# MSSRP-Temperature_System_beta_2layer.net
KiCad netlist of a schematic drawn in EAGLE
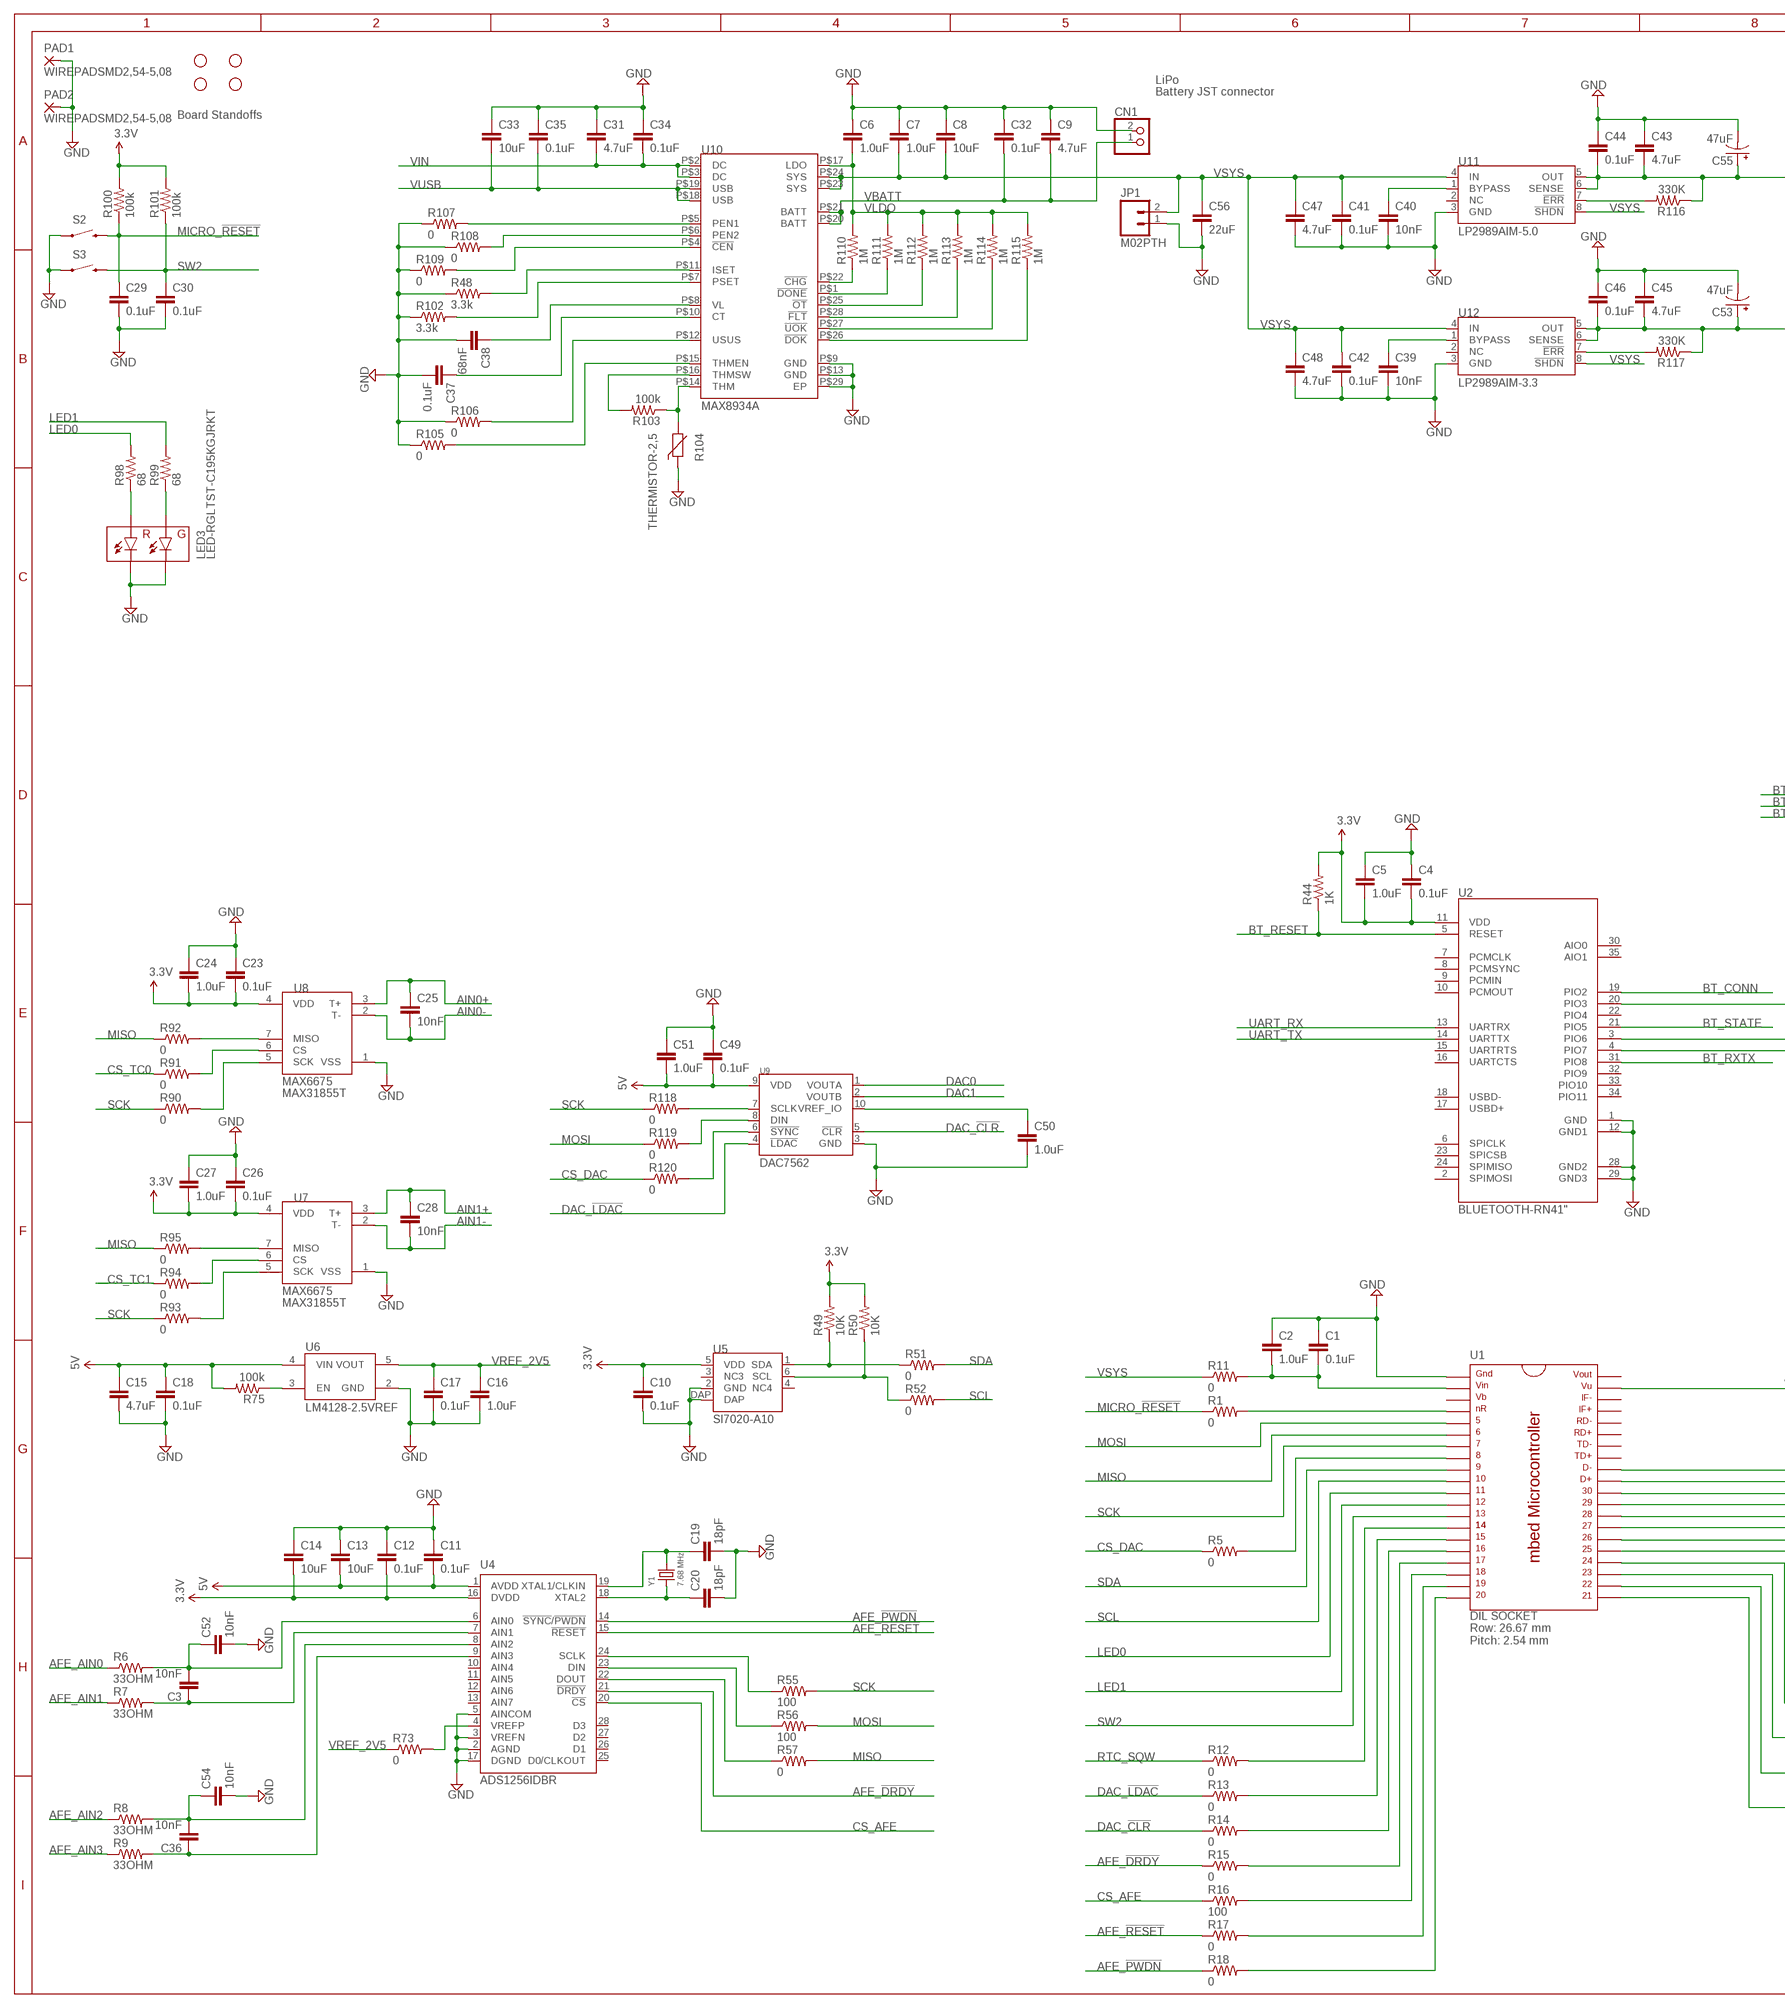
[diagram p0: schematic, sheet 1, part 1 of 2]
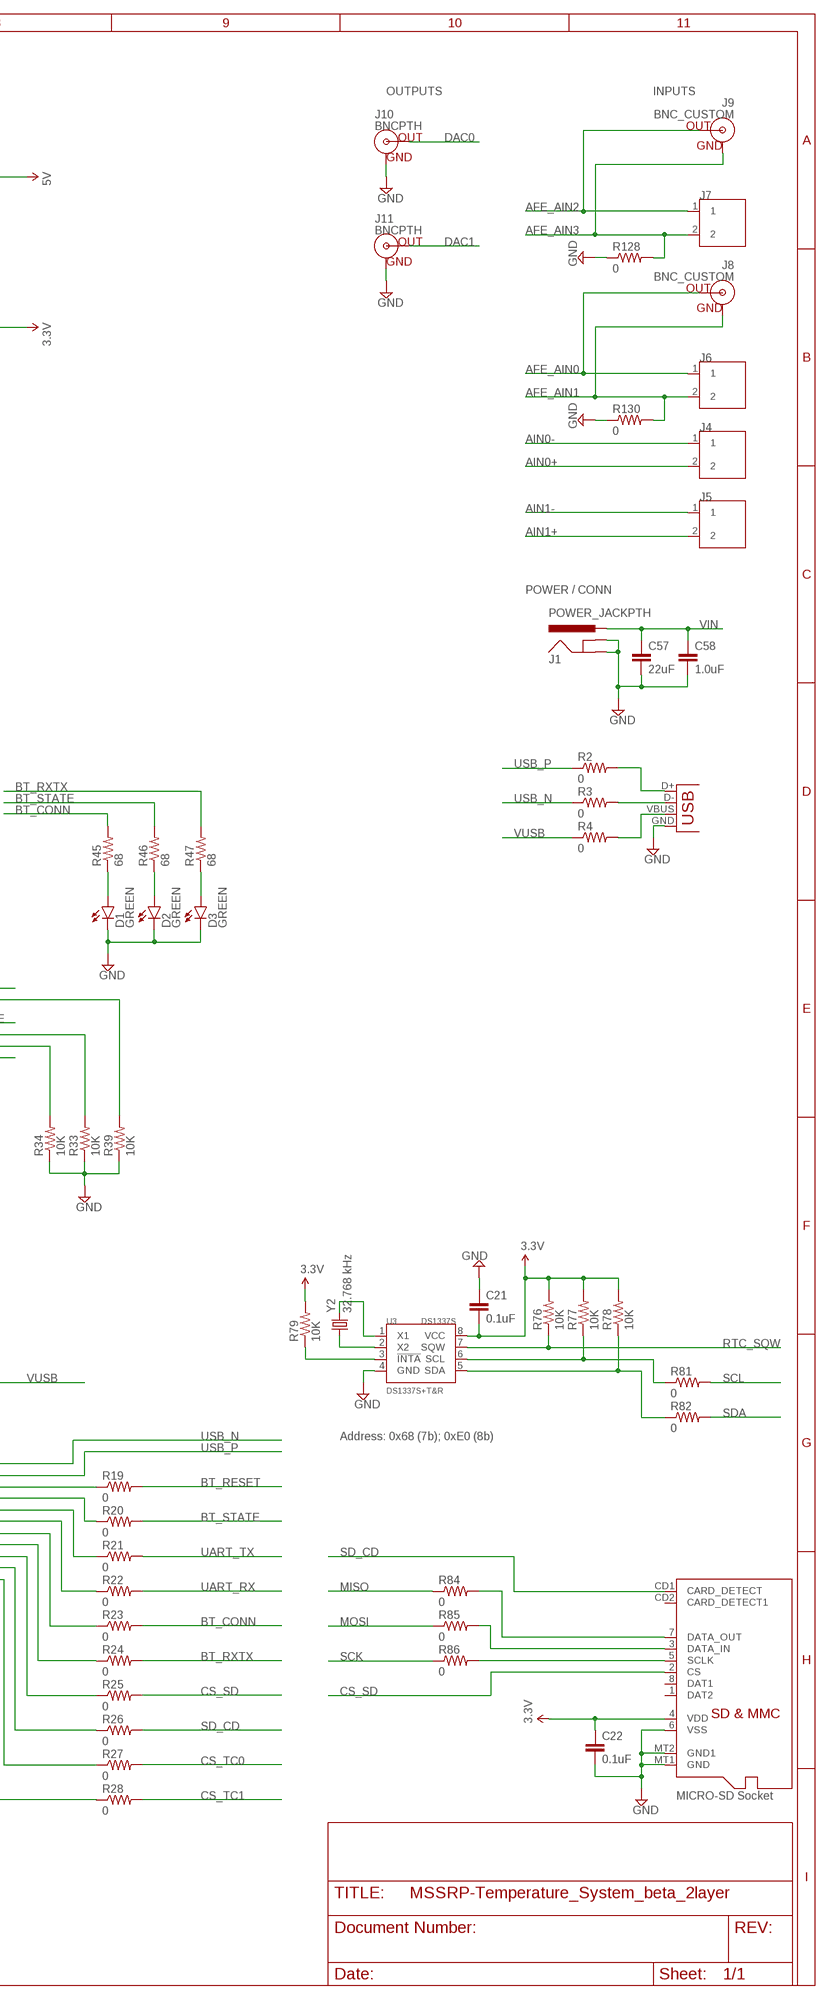
[diagram p1: schematic, sheet 1, part 2 of 2]

(export (version "E")
  (design (tool "Eeschema 10.0.6"))
  (components
    (comp (ref "C1")
      (value "0.1uF")
      (footprint "eagle-import:0603-CAP")
      (libsource (lib "eagle-import") (part "0.1UF-25V-5%(0603)"))
    )
    (comp (ref "C2")
      (value "1.0uF")
      (footprint "eagle-import:0603-CAP")
      (libsource (lib "eagle-import") (part "1.0UF-16V-10%(0603)"))
    )
    (comp (ref "C3")
      (value "10nF")
      (footprint "eagle-import:0603-CAP")
      (libsource (lib "eagle-import") (part "10NF/10000PF-50V-10%(0603)"))
    )
    (comp (ref "C4")
      (value "0.1uF")
      (footprint "eagle-import:0603-CAP")
      (libsource (lib "eagle-import") (part "0.1UF-25V-5%(0603)"))
    )
    (comp (ref "C5")
      (value "1.0uF")
      (footprint "eagle-import:0603-CAP")
      (libsource (lib "eagle-import") (part "1.0UF-16V-10%(0603)"))
    )
    (comp (ref "C6")
      (value "1.0uF")
      (footprint "eagle-import:0603-CAP")
      (libsource (lib "eagle-import") (part "1.0UF-16V-10%(0603)"))
    )
    (comp (ref "C7")
      (value "1.0uF")
      (footprint "eagle-import:0603-CAP")
      (libsource (lib "eagle-import") (part "1.0UF-16V-10%(0603)"))
    )
    (comp (ref "C8")
      (value "10uF")
      (footprint "eagle-import:0603-CAP")
      (libsource (lib "eagle-import") (part "10UF-6.3V-20%(0603)"))
    )
    (comp (ref "C9")
      (value "4.7uF")
      (footprint "eagle-import:0603-CAP")
      (libsource (lib "eagle-import") (part "4.7UF-6.3V-10%(0603)0603"))
    )
    (comp (ref "C10")
      (value "0.1uF")
      (footprint "eagle-import:0603-CAP")
      (libsource (lib "eagle-import") (part "0.1UF-25V-5%(0603)"))
    )
    (comp (ref "C11")
      (value "0.1uF")
      (footprint "eagle-import:0603-CAP")
      (libsource (lib "eagle-import") (part "0.1UF-25V-5%(0603)"))
    )
    (comp (ref "C12")
      (value "0.1uF")
      (footprint "eagle-import:0603-CAP")
      (libsource (lib "eagle-import") (part "0.1UF-25V-5%(0603)"))
    )
    (comp (ref "C13")
      (value "10uF")
      (footprint "eagle-import:0603-CAP")
      (libsource (lib "eagle-import") (part "10UF-6.3V-20%(0603)"))
    )
    (comp (ref "C14")
      (value "10uF")
      (footprint "eagle-import:0603-CAP")
      (libsource (lib "eagle-import") (part "10UF-6.3V-20%(0603)"))
    )
    (comp (ref "C15")
      (value "4.7uF")
      (footprint "eagle-import:0603-CAP")
      (libsource (lib "eagle-import") (part "4.7UF-6.3V-10%(0603)0603"))
    )
    (comp (ref "C16")
      (value "1.0uF")
      (footprint "eagle-import:0603-CAP")
      (libsource (lib "eagle-import") (part "1.0UF-16V-10%(0603)"))
    )
    (comp (ref "C17")
      (value "0.1uF")
      (footprint "eagle-import:0603-CAP")
      (libsource (lib "eagle-import") (part "0.1UF-25V-5%(0603)"))
    )
    (comp (ref "C18")
      (value "0.1uF")
      (footprint "eagle-import:0603-CAP")
      (libsource (lib "eagle-import") (part "0.1UF-25V-5%(0603)"))
    )
    (comp (ref "C19")
      (value "18pF")
      (footprint "eagle-import:0603-CAP")
      (libsource (lib "eagle-import") (part "18PF-50V-5%(0603)"))
    )
    (comp (ref "C20")
      (value "18pF")
      (footprint "eagle-import:0603-CAP")
      (libsource (lib "eagle-import") (part "18PF-50V-5%(0603)"))
    )
    (comp (ref "C21")
      (value "0.1uF")
      (footprint "eagle-import:0603-CAP")
      (libsource (lib "eagle-import") (part "0.1UF-25V-5%(0603)"))
    )
    (comp (ref "C22")
      (value "0.1uF")
      (footprint "eagle-import:0603-CAP")
      (libsource (lib "eagle-import") (part "0.1UF-25V-5%(0603)"))
    )
    (comp (ref "C23")
      (value "0.1uF")
      (footprint "eagle-import:0603-CAP")
      (libsource (lib "eagle-import") (part "0.1UF-25V-5%(0603)"))
    )
    (comp (ref "C24")
      (value "1.0uF")
      (footprint "eagle-import:0603-CAP")
      (libsource (lib "eagle-import") (part "1.0UF-16V-10%(0603)"))
    )
    (comp (ref "C25")
      (value "10nF")
      (footprint "eagle-import:0603-CAP")
      (libsource (lib "eagle-import") (part "10NF/10000PF-50V-10%(0603)"))
    )
    (comp (ref "C26")
      (value "0.1uF")
      (footprint "eagle-import:0603-CAP")
      (libsource (lib "eagle-import") (part "0.1UF-25V-5%(0603)"))
    )
    (comp (ref "C27")
      (value "1.0uF")
      (footprint "eagle-import:0603-CAP")
      (libsource (lib "eagle-import") (part "1.0UF-16V-10%(0603)"))
    )
    (comp (ref "C28")
      (value "10nF")
      (footprint "eagle-import:0603-CAP")
      (libsource (lib "eagle-import") (part "10NF/10000PF-50V-10%(0603)"))
    )
    (comp (ref "C29")
      (value "0.1uF")
      (footprint "eagle-import:0603-CAP")
      (libsource (lib "eagle-import") (part "0.1UF-25V-5%(0603)"))
    )
    (comp (ref "C30")
      (value "0.1uF")
      (footprint "eagle-import:0603-CAP")
      (libsource (lib "eagle-import") (part "0.1UF-25V-5%(0603)"))
    )
    (comp (ref "C31")
      (value "4.7uF")
      (footprint "eagle-import:0603-CAP")
      (libsource (lib "eagle-import") (part "4.7UF-6.3V-10%(0603)0603"))
    )
    (comp (ref "C32")
      (value "0.1uF")
      (footprint "eagle-import:0603-CAP")
      (libsource (lib "eagle-import") (part "0.1UF-25V-5%(0603)"))
    )
    (comp (ref "C33")
      (value "10uF")
      (footprint "eagle-import:0603-CAP")
      (libsource (lib "eagle-import") (part "10UF-6.3V-20%(0603)"))
    )
    (comp (ref "C34")
      (value "0.1uF")
      (footprint "eagle-import:0603-CAP")
      (libsource (lib "eagle-import") (part "0.1UF-25V-5%(0603)"))
    )
    (comp (ref "C35")
      (value "0.1uF")
      (footprint "eagle-import:0603-CAP")
      (libsource (lib "eagle-import") (part "0.1UF-25V-5%(0603)"))
    )
    (comp (ref "C36")
      (value "10nF")
      (footprint "eagle-import:0603-CAP")
      (libsource (lib "eagle-import") (part "10NF/10000PF-50V-10%(0603)"))
    )
    (comp (ref "C37")
      (value "0.1uF")
      (footprint "eagle-import:0603-CAP")
      (libsource (lib "eagle-import") (part "0.1UF-25V-5%(0603)"))
    )
    (comp (ref "C38")
      (value "68nF")
      (footprint "eagle-import:0603-CAP")
      (libsource (lib "eagle-import") (part "0.1UF-25V-5%(0603)"))
    )
    (comp (ref "C39")
      (value "10nF")
      (footprint "eagle-import:0603-CAP")
      (libsource (lib "eagle-import") (part "10NF/10000PF-50V-10%(0603)"))
    )
    (comp (ref "C40")
      (value "10nF")
      (footprint "eagle-import:0603-CAP")
      (libsource (lib "eagle-import") (part "10NF/10000PF-50V-10%(0603)"))
    )
    (comp (ref "C41")
      (value "0.1uF")
      (footprint "eagle-import:0603-CAP")
      (libsource (lib "eagle-import") (part "0.1UF-25V-5%(0603)"))
    )
    (comp (ref "C42")
      (value "0.1uF")
      (footprint "eagle-import:0603-CAP")
      (libsource (lib "eagle-import") (part "0.1UF-25V-5%(0603)"))
    )
    (comp (ref "C43")
      (value "4.7uF")
      (footprint "eagle-import:0603-CAP")
      (libsource (lib "eagle-import") (part "4.7UF-6.3V-10%(0603)0603"))
    )
    (comp (ref "C44")
      (value "0.1uF")
      (footprint "eagle-import:0603-CAP")
      (libsource (lib "eagle-import") (part "0.1UF-25V-5%(0603)"))
    )
    (comp (ref "C45")
      (value "4.7uF")
      (footprint "eagle-import:0603-CAP")
      (libsource (lib "eagle-import") (part "4.7UF-6.3V-10%(0603)0603"))
    )
    (comp (ref "C46")
      (value "0.1uF")
      (footprint "eagle-import:0603-CAP")
      (libsource (lib "eagle-import") (part "0.1UF-25V-5%(0603)"))
    )
    (comp (ref "C47")
      (value "4.7uF")
      (footprint "eagle-import:0603-CAP")
      (libsource (lib "eagle-import") (part "4.7UF-6.3V-10%(0603)0603"))
    )
    (comp (ref "C48")
      (value "4.7uF")
      (footprint "eagle-import:0603-CAP")
      (libsource (lib "eagle-import") (part "4.7UF-6.3V-10%(0603)0603"))
    )
    (comp (ref "C49")
      (value "0.1uF")
      (footprint "eagle-import:0603-CAP")
      (libsource (lib "eagle-import") (part "0.1UF-25V-5%(0603)"))
    )
    (comp (ref "C50")
      (value "1.0uF")
      (footprint "eagle-import:0603-CAP")
      (libsource (lib "eagle-import") (part "1.0UF-16V-10%(0603)"))
    )
    (comp (ref "C51")
      (value "1.0uF")
      (footprint "eagle-import:0603-CAP")
      (libsource (lib "eagle-import") (part "1.0UF-16V-10%(0603)"))
    )
    (comp (ref "C52")
      (value "10nF")
      (footprint "eagle-import:0603-CAP")
      (libsource (lib "eagle-import") (part "10NF/10000PF-50V-10%(0603)"))
    )
    (comp (ref "C53")
      (value "47uF")
      (footprint "eagle-import:EIA3528")
      (libsource (lib "eagle-import") (part "47UF-10V-10%(TANT)"))
    )
    (comp (ref "C54")
      (value "10nF")
      (footprint "eagle-import:0603-CAP")
      (libsource (lib "eagle-import") (part "10NF/10000PF-50V-10%(0603)"))
    )
    (comp (ref "C55")
      (value "47uF")
      (footprint "eagle-import:EIA3528")
      (libsource (lib "eagle-import") (part "47UF-10V-10%(TANT)"))
    )
    (comp (ref "C56")
      (value "22uF")
      (footprint "eagle-import:0805")
      (libsource (lib "eagle-import") (part "22UF-6.3V-20%(0805)"))
    )
    (comp (ref "C57")
      (value "22uF")
      (footprint "eagle-import:1210")
      (libsource (lib "eagle-import") (part "22UF-16V-20%-(1210)"))
    )
    (comp (ref "C58")
      (value "1.0uF")
      (footprint "eagle-import:0603-CAP")
      (libsource (lib "eagle-import") (part "1.0UF-16V-10%(0603)"))
    )
    (comp (ref "CN1")
      (value "JST_2PIN-THM-RA")
      (footprint "eagle-import:JST-PH-2-THM-RA")
      (libsource (lib "eagle-import") (part "JST_2PIN-THM-RA"))
    )
    (comp (ref "D1")
      (value "GREEN")
      (footprint "eagle-import:LED-0603")
      (libsource (lib "eagle-import") (part "LED-GREEN0603"))
    )
    (comp (ref "D2")
      (value "GREEN")
      (footprint "eagle-import:LED-0603")
      (libsource (lib "eagle-import") (part "LED-GREEN0603"))
    )
    (comp (ref "D3")
      (value "GREEN")
      (footprint "eagle-import:LED-0603")
      (libsource (lib "eagle-import") (part "LED-GREEN0603"))
    )
    (comp (ref "J1")
      (value "POWER_JACKPTH")
      (footprint "eagle-import:POWER_JACK_PTH")
      (libsource (lib "eagle-import") (part "POWER_JACKPTH"))
    )
    (comp (ref "J2")
      (value "USBSMD")
      (footprint "eagle-import:USB-MINIB")
      (libsource (lib "eagle-import") (part "USBSMD"))
    )
    (comp (ref "J4")
      (value "TE-2-TERMBLOCK")
      (footprint "eagle-import:TE-2-TERMBLOCK")
      (libsource (lib "eagle-import") (part "TE-2-TERMBLOCK"))
    )
    (comp (ref "J5")
      (value "TE-2-TERMBLOCK")
      (footprint "eagle-import:TE-2-TERMBLOCK")
      (libsource (lib "eagle-import") (part "TE-2-TERMBLOCK"))
    )
    (comp (ref "J6")
      (value "TE-2-TERMBLOCK")
      (footprint "eagle-import:TE-2-TERMBLOCK")
      (libsource (lib "eagle-import") (part "TE-2-TERMBLOCK"))
    )
    (comp (ref "J7")
      (value "TE-2-TERMBLOCK")
      (footprint "eagle-import:TE-2-TERMBLOCK")
      (libsource (lib "eagle-import") (part "TE-2-TERMBLOCK"))
    )
    (comp (ref "J8")
      (value "BNC_CUSTOM")
      (footprint "eagle-import:BNC_CUSTOM")
      (libsource (lib "eagle-import") (part "BNC_CUSTOM"))
    )
    (comp (ref "J9")
      (value "BNC_CUSTOM")
      (footprint "eagle-import:BNC_CUSTOM")
      (libsource (lib "eagle-import") (part "BNC_CUSTOM"))
    )
    (comp (ref "J10")
      (value "BNCPTH")
      (footprint "eagle-import:BNC")
      (libsource (lib "eagle-import") (part "BNCPTH"))
    )
    (comp (ref "J11")
      (value "BNCPTH")
      (footprint "eagle-import:BNC")
      (libsource (lib "eagle-import") (part "BNCPTH"))
    )
    (comp (ref "JP1")
      (value "M02PTH")
      (footprint "eagle-import:1X02")
      (libsource (lib "eagle-import") (part "M02PTH"))
    )
    (comp (ref "LED3")
      (value "LED-RGLTST-C195KGJRKT")
      (footprint "eagle-import:LTST-C195KGJRKT")
      (libsource (lib "eagle-import") (part "LED-RGLTST-C195KGJRKT"))
    )
    (comp (ref "PAD1")
      (value "WIREPADSMD2,54-5,08")
      (footprint "eagle-import:SMD2,54-5,08")
      (libsource (lib "eagle-import") (part "WIREPADSMD2,54-5,08"))
    )
    (comp (ref "PAD2")
      (value "WIREPADSMD2,54-5,08")
      (footprint "eagle-import:SMD2,54-5,08")
      (libsource (lib "eagle-import") (part "WIREPADSMD2,54-5,08"))
    )
    (comp (ref "R1")
      (value "0")
      (footprint "eagle-import:0603")
      (libsource (lib "eagle-import") (part "0OHM1/10W5%(0603)"))
    )
    (comp (ref "R2")
      (value "0")
      (footprint "eagle-import:0603")
      (libsource (lib "eagle-import") (part "0OHM1/10W5%(0603)"))
    )
    (comp (ref "R3")
      (value "0")
      (footprint "eagle-import:0603")
      (libsource (lib "eagle-import") (part "0OHM1/10W5%(0603)"))
    )
    (comp (ref "R4")
      (value "0")
      (footprint "eagle-import:0603")
      (libsource (lib "eagle-import") (part "0OHM1/10W5%(0603)"))
    )
    (comp (ref "R5")
      (value "0")
      (footprint "eagle-import:0603")
      (libsource (lib "eagle-import") (part "0OHM1/10W5%(0603)"))
    )
    (comp (ref "R6")
      (value "33OHM")
      (footprint "eagle-import:0603")
      (libsource (lib "eagle-import") (part "33OHM1/10W1%(0603)"))
    )
    (comp (ref "R7")
      (value "33OHM")
      (footprint "eagle-import:0603")
      (libsource (lib "eagle-import") (part "33OHM1/10W1%(0603)"))
    )
    (comp (ref "R8")
      (value "33OHM")
      (footprint "eagle-import:0603")
      (libsource (lib "eagle-import") (part "33OHM1/10W1%(0603)"))
    )
    (comp (ref "R9")
      (value "33OHM")
      (footprint "eagle-import:0603")
      (libsource (lib "eagle-import") (part "33OHM1/10W1%(0603)"))
    )
    (comp (ref "R11")
      (value "0")
      (footprint "eagle-import:0603")
      (libsource (lib "eagle-import") (part "0OHM1/10W5%(0603)"))
    )
    (comp (ref "R12")
      (value "0")
      (footprint "eagle-import:0603")
      (libsource (lib "eagle-import") (part "0OHM1/10W5%(0603)"))
    )
    (comp (ref "R13")
      (value "0")
      (footprint "eagle-import:0603")
      (libsource (lib "eagle-import") (part "0OHM1/10W5%(0603)"))
    )
    (comp (ref "R14")
      (value "0")
      (footprint "eagle-import:0603")
      (libsource (lib "eagle-import") (part "0OHM1/10W5%(0603)"))
    )
    (comp (ref "R15")
      (value "0")
      (footprint "eagle-import:0603")
      (libsource (lib "eagle-import") (part "0OHM1/10W5%(0603)"))
    )
    (comp (ref "R16")
      (value "100")
      (footprint "eagle-import:0603-RES")
      (libsource (lib "eagle-import") (part "100OHM1/10W1%(0603)"))
    )
    (comp (ref "R17")
      (value "0")
      (footprint "eagle-import:0603")
      (libsource (lib "eagle-import") (part "0OHM1/10W5%(0603)"))
    )
    (comp (ref "R18")
      (value "0")
      (footprint "eagle-import:0603")
      (libsource (lib "eagle-import") (part "0OHM1/10W5%(0603)"))
    )
    (comp (ref "R19")
      (value "0")
      (footprint "eagle-import:0603")
      (libsource (lib "eagle-import") (part "0OHM1/10W5%(0603)"))
    )
    (comp (ref "R20")
      (value "0")
      (footprint "eagle-import:0603")
      (libsource (lib "eagle-import") (part "0OHM1/10W5%(0603)"))
    )
    (comp (ref "R21")
      (value "0")
      (footprint "eagle-import:0603")
      (libsource (lib "eagle-import") (part "0OHM1/10W5%(0603)"))
    )
    (comp (ref "R22")
      (value "0")
      (footprint "eagle-import:0603")
      (libsource (lib "eagle-import") (part "0OHM1/10W5%(0603)"))
    )
    (comp (ref "R23")
      (value "0")
      (footprint "eagle-import:0603")
      (libsource (lib "eagle-import") (part "0OHM1/10W5%(0603)"))
    )
    (comp (ref "R24")
      (value "0")
      (footprint "eagle-import:0603")
      (libsource (lib "eagle-import") (part "0OHM1/10W5%(0603)"))
    )
    (comp (ref "R25")
      (value "0")
      (footprint "eagle-import:0603")
      (libsource (lib "eagle-import") (part "0OHM1/10W5%(0603)"))
    )
    (comp (ref "R26")
      (value "0")
      (footprint "eagle-import:0603")
      (libsource (lib "eagle-import") (part "0OHM1/10W5%(0603)"))
    )
    (comp (ref "R27")
      (value "0")
      (footprint "eagle-import:0603")
      (libsource (lib "eagle-import") (part "0OHM1/10W5%(0603)"))
    )
    (comp (ref "R28")
      (value "0")
      (footprint "eagle-import:0603")
      (libsource (lib "eagle-import") (part "0OHM1/10W5%(0603)"))
    )
    (comp (ref "R33")
      (value "10K")
      (footprint "eagle-import:0603-RES")
      (libsource (lib "eagle-import") (part "10KOHM1/10W1%(0603)0603"))
    )
    (comp (ref "R34")
      (value "10K")
      (footprint "eagle-import:0603-RES")
      (libsource (lib "eagle-import") (part "10KOHM1/10W1%(0603)0603"))
    )
    (comp (ref "R39")
      (value "10K")
      (footprint "eagle-import:0603-RES")
      (libsource (lib "eagle-import") (part "10KOHM1/10W1%(0603)0603"))
    )
    (comp (ref "R44")
      (value "1K")
      (footprint "eagle-import:0603-RES")
      (libsource (lib "eagle-import") (part "1KOHM1/10W1%(0603)"))
    )
    (comp (ref "R45")
      (value "68")
      (footprint "eagle-import:0603-RES")
      (libsource (lib "eagle-import") (part "390OHM1/10W1%(0603)"))
    )
    (comp (ref "R46")
      (value "68")
      (footprint "eagle-import:0603-RES")
      (libsource (lib "eagle-import") (part "390OHM1/10W1%(0603)"))
    )
    (comp (ref "R47")
      (value "68")
      (footprint "eagle-import:0603-RES")
      (libsource (lib "eagle-import") (part "390OHM1/10W1%(0603)"))
    )
    (comp (ref "R48")
      (value "3.3k")
      (footprint "eagle-import:0603-RES")
      (libsource (lib "eagle-import") (part "3.3MOHM-1/10W-1%(0603)"))
    )
    (comp (ref "R49")
      (value "10K")
      (footprint "eagle-import:0603-RES")
      (libsource (lib "eagle-import") (part "10KOHM1/10W1%(0603)0603"))
    )
    (comp (ref "R50")
      (value "10K")
      (footprint "eagle-import:0603-RES")
      (libsource (lib "eagle-import") (part "10KOHM1/10W1%(0603)0603"))
    )
    (comp (ref "R51")
      (value "0")
      (footprint "eagle-import:0603")
      (libsource (lib "eagle-import") (part "0OHM1/10W5%(0603)"))
    )
    (comp (ref "R52")
      (value "0")
      (footprint "eagle-import:0603")
      (libsource (lib "eagle-import") (part "0OHM1/10W5%(0603)"))
    )
    (comp (ref "R55")
      (value "100")
      (footprint "eagle-import:0603-RES")
      (libsource (lib "eagle-import") (part "100OHM1/10W1%(0603)"))
    )
    (comp (ref "R56")
      (value "100")
      (footprint "eagle-import:0603-RES")
      (libsource (lib "eagle-import") (part "100OHM1/10W1%(0603)"))
    )
    (comp (ref "R57")
      (value "0")
      (footprint "eagle-import:0603")
      (libsource (lib "eagle-import") (part "0OHM1/10W5%(0603)"))
    )
    (comp (ref "R73")
      (value "0")
      (footprint "eagle-import:0603")
      (libsource (lib "eagle-import") (part "0OHM1/10W5%(0603)"))
    )
    (comp (ref "R75")
      (value "100k")
      (footprint "eagle-import:0603-RES")
      (libsource (lib "eagle-import") (part "100KOHM1/10W1%(0603)"))
    )
    (comp (ref "R76")
      (value "10K")
      (footprint "eagle-import:0603-RES")
      (libsource (lib "eagle-import") (part "10KOHM1/10W1%(0603)0603"))
    )
    (comp (ref "R77")
      (value "10K")
      (footprint "eagle-import:0603-RES")
      (libsource (lib "eagle-import") (part "10KOHM1/10W1%(0603)0603"))
    )
    (comp (ref "R78")
      (value "10K")
      (footprint "eagle-import:0603-RES")
      (libsource (lib "eagle-import") (part "10KOHM1/10W1%(0603)0603"))
    )
    (comp (ref "R79")
      (value "10K")
      (footprint "eagle-import:0603-RES")
      (libsource (lib "eagle-import") (part "10KOHM1/10W1%(0603)0603"))
    )
    (comp (ref "R81")
      (value "0")
      (footprint "eagle-import:0603")
      (libsource (lib "eagle-import") (part "0OHM1/10W5%(0603)"))
    )
    (comp (ref "R82")
      (value "0")
      (footprint "eagle-import:0603")
      (libsource (lib "eagle-import") (part "0OHM1/10W5%(0603)"))
    )
    (comp (ref "R84")
      (value "0")
      (footprint "eagle-import:0603")
      (libsource (lib "eagle-import") (part "0OHM1/10W5%(0603)"))
    )
    (comp (ref "R85")
      (value "0")
      (footprint "eagle-import:0603")
      (libsource (lib "eagle-import") (part "0OHM1/10W5%(0603)"))
    )
    (comp (ref "R86")
      (value "0")
      (footprint "eagle-import:0603")
      (libsource (lib "eagle-import") (part "0OHM1/10W5%(0603)"))
    )
    (comp (ref "R90")
      (value "0")
      (footprint "eagle-import:0603")
      (libsource (lib "eagle-import") (part "0OHM1/10W5%(0603)"))
    )
    (comp (ref "R91")
      (value "0")
      (footprint "eagle-import:0603")
      (libsource (lib "eagle-import") (part "0OHM1/10W5%(0603)"))
    )
    (comp (ref "R92")
      (value "0")
      (footprint "eagle-import:0603")
      (libsource (lib "eagle-import") (part "0OHM1/10W5%(0603)"))
    )
    (comp (ref "R93")
      (value "0")
      (footprint "eagle-import:0603")
      (libsource (lib "eagle-import") (part "0OHM1/10W5%(0603)"))
    )
    (comp (ref "R94")
      (value "0")
      (footprint "eagle-import:0603")
      (libsource (lib "eagle-import") (part "0OHM1/10W5%(0603)"))
    )
    (comp (ref "R95")
      (value "0")
      (footprint "eagle-import:0603")
      (libsource (lib "eagle-import") (part "0OHM1/10W5%(0603)"))
    )
    (comp (ref "R98")
      (value "68")
      (footprint "eagle-import:0603-RES")
      (libsource (lib "eagle-import") (part "470OHM1/10W1%(0603)"))
    )
    (comp (ref "R99")
      (value "68")
      (footprint "eagle-import:0603-RES")
      (libsource (lib "eagle-import") (part "470OHM1/10W1%(0603)"))
    )
    (comp (ref "R100")
      (value "100k")
      (footprint "eagle-import:0603-RES")
      (libsource (lib "eagle-import") (part "100KOHM1/10W1%(0603)"))
    )
    (comp (ref "R101")
      (value "100k")
      (footprint "eagle-import:0603-RES")
      (libsource (lib "eagle-import") (part "100KOHM1/10W1%(0603)"))
    )
    (comp (ref "R102")
      (value "3.3k")
      (footprint "eagle-import:0603-RES")
      (libsource (lib "eagle-import") (part "3.3MOHM-1/10W-1%(0603)"))
    )
    (comp (ref "R103")
      (value "100k")
      (footprint "eagle-import:0603-RES")
      (libsource (lib "eagle-import") (part "100OHM1/10W1%(0603)"))
    )
    (comp (ref "R104")
      (value "THERMISTOR-2,5")
      (footprint "eagle-import:RS-2,5")
      (libsource (lib "eagle-import") (part "THERMISTOR-2,5"))
    )
    (comp (ref "R105")
      (value "0")
      (footprint "eagle-import:0603")
      (libsource (lib "eagle-import") (part "0OHM1/10W5%(0603)"))
    )
    (comp (ref "R106")
      (value "0")
      (footprint "eagle-import:0603")
      (libsource (lib "eagle-import") (part "0OHM1/10W5%(0603)"))
    )
    (comp (ref "R107")
      (value "0")
      (footprint "eagle-import:0603")
      (libsource (lib "eagle-import") (part "0OHM1/10W5%(0603)"))
    )
    (comp (ref "R108")
      (value "0")
      (footprint "eagle-import:0603")
      (libsource (lib "eagle-import") (part "0OHM1/10W5%(0603)"))
    )
    (comp (ref "R109")
      (value "0")
      (footprint "eagle-import:0603")
      (libsource (lib "eagle-import") (part "0OHM1/10W5%(0603)"))
    )
    (comp (ref "R110")
      (value "1M")
      (footprint "eagle-import:0603-RES")
      (libsource (lib "eagle-import") (part "330KOHM1/10W1%(0603)0603"))
    )
    (comp (ref "R111")
      (value "1M")
      (footprint "eagle-import:0603-RES")
      (libsource (lib "eagle-import") (part "330KOHM1/10W1%(0603)0603"))
    )
    (comp (ref "R112")
      (value "1M")
      (footprint "eagle-import:0603-RES")
      (libsource (lib "eagle-import") (part "330KOHM1/10W1%(0603)0603"))
    )
    (comp (ref "R113")
      (value "1M")
      (footprint "eagle-import:0603-RES")
      (libsource (lib "eagle-import") (part "330KOHM1/10W1%(0603)0603"))
    )
    (comp (ref "R114")
      (value "1M")
      (footprint "eagle-import:0603-RES")
      (libsource (lib "eagle-import") (part "330KOHM1/10W1%(0603)0603"))
    )
    (comp (ref "R115")
      (value "1M")
      (footprint "eagle-import:0603-RES")
      (libsource (lib "eagle-import") (part "330KOHM1/10W1%(0603)0603"))
    )
    (comp (ref "R116")
      (value "330K")
      (footprint "eagle-import:0603-RES")
      (libsource (lib "eagle-import") (part "330KOHM1/10W1%(0603)0603"))
    )
    (comp (ref "R117")
      (value "330K")
      (footprint "eagle-import:0603-RES")
      (libsource (lib "eagle-import") (part "330KOHM1/10W1%(0603)0603"))
    )
    (comp (ref "R118")
      (value "0")
      (footprint "eagle-import:0603")
      (libsource (lib "eagle-import") (part "0OHM1/10W5%(0603)"))
    )
    (comp (ref "R119")
      (value "0")
      (footprint "eagle-import:0603")
      (libsource (lib "eagle-import") (part "0OHM1/10W5%(0603)"))
    )
    (comp (ref "R120")
      (value "0")
      (footprint "eagle-import:0603")
      (libsource (lib "eagle-import") (part "0OHM1/10W5%(0603)"))
    )
    (comp (ref "R128")
      (value "0")
      (footprint "eagle-import:0603")
      (libsource (lib "eagle-import") (part "0OHM1/10W5%(0603)"))
    )
    (comp (ref "R130")
      (value "0")
      (footprint "eagle-import:0603")
      (libsource (lib "eagle-import") (part "0OHM1/10W5%(0603)"))
    )
    (comp (ref "S2")
      (value "SWITCH-MOMENTARY-2-SMD-1101NE")
      (footprint "eagle-import:TACTILE-SWITCH-1101NE")
      (libsource (lib "eagle-import") (part "SWITCH-MOMENTARY-2-SMD-1101NE"))
    )
    (comp (ref "S3")
      (value "SWITCH-MOMENTARY-2-SMD-1101NE")
      (footprint "eagle-import:TACTILE-SWITCH-1101NE")
      (libsource (lib "eagle-import") (part "SWITCH-MOMENTARY-2-SMD-1101NE"))
    )
    (comp (ref "STANDOFF1")
      (value "STAND-OFF")
      (footprint "eagle-import:STAND-OFF")
      (libsource (lib "eagle-import") (part "STAND-OFF"))
    )
    (comp (ref "STANDOFF2")
      (value "STAND-OFF")
      (footprint "eagle-import:STAND-OFF")
      (libsource (lib "eagle-import") (part "STAND-OFF"))
    )
    (comp (ref "STANDOFF3")
      (value "STAND-OFF")
      (footprint "eagle-import:STAND-OFF")
      (libsource (lib "eagle-import") (part "STAND-OFF"))
    )
    (comp (ref "STANDOFF4")
      (value "STAND-OFF")
      (footprint "eagle-import:STAND-OFF")
      (libsource (lib "eagle-import") (part "STAND-OFF"))
    )
    (comp (ref "U$1")
      (value "MICROSD")
      (footprint "eagle-import:MICROSD")
      (libsource (lib "eagle-import") (part "MICROSD"))
    )
    (comp (ref "U1")
      (value "MBED")
      (footprint "eagle-import:DIL40_0.9")
      (libsource (lib "eagle-import") (part "MBED"))
    )
    (comp (ref "U2")
      (value "BLUETOOTH-RN41\"")
      (footprint "eagle-import:RN41")
      (libsource (lib "eagle-import") (part "BLUETOOTH-RN41{dblquote}"))
    )
    (comp (ref "U3")
      (value "DS1337S+T&R")
      (footprint "eagle-import:SOIC8")
      (libsource (lib "eagle-import") (part "DS1337S+T&R"))
    )
    (comp (ref "U4")
      (value "ADS1256IDBR")
      (footprint "eagle-import:SSOP28")
      (libsource (lib "eagle-import") (part "ADS1256IDBR"))
    )
    (comp (ref "U5")
      (value "SI7020-A10")
      (footprint "eagle-import:DFN6")
      (libsource (lib "eagle-import") (part "SI7020-A10"))
    )
    (comp (ref "U6")
      (value "LM4128-2.5VREF")
      (footprint "eagle-import:SOT23-5")
      (libsource (lib "eagle-import") (part "LM4128-2.5VREF"))
    )
    (comp (ref "U7")
      (value "MAX6675")
      (footprint "eagle-import:SO08-MAX6675")
      (libsource (lib "eagle-import") (part "MAX6675"))
    )
    (comp (ref "U8")
      (value "MAX6675")
      (footprint "eagle-import:SO08-MAX6675")
      (libsource (lib "eagle-import") (part "MAX6675"))
    )
    (comp (ref "U9")
      (value "DAC7562")
      (footprint "eagle-import:MSOP10")
      (libsource (lib "eagle-import") (part "DAC7562"))
    )
    (comp (ref "U10")
      (value "MAX8934A")
      (footprint "eagle-import:QFN28")
      (libsource (lib "eagle-import") (part "MAX8934A"))
    )
    (comp (ref "U11")
      (value "LP2989AIM")
      (footprint "eagle-import:SOIC8")
      (libsource (lib "eagle-import") (part "LP2989AIM"))
    )
    (comp (ref "U12")
      (value "LP2989AIM")
      (footprint "eagle-import:SOIC8")
      (libsource (lib "eagle-import") (part "LP2989AIM"))
    )
    (comp (ref "Y1")
      (value "7.68 MHz")
      (footprint "eagle-import:HC49UP")
      (libsource (lib "eagle-import") (part "microbuilder_CRYSTALSMD"))
    )
    (comp (ref "Y2")
      (value "32.768 kHz")
      (footprint "eagle-import:HC49UP")
      (libsource (lib "eagle-import") (part "CRYSTALSMD"))
    )
  )
  (nets
    (net (code "1") (name "/AFE_AIN0") (class "Default")
      (node (ref "J6") (pin "1") (pinfunction "1_1") (pintype "passive"))
      (node (ref "J8") (pin "S") (pinfunction "OUT_S") (pintype "bidirectional"))
      (node (ref "R6") (pin "1") (pinfunction "1_1") (pintype "passive"))
    )
    (net (code "2") (name "/AFE_AIN1") (class "Default")
      (node (ref "J6") (pin "2") (pinfunction "2_2") (pintype "passive"))
      (node (ref "J8") (pin "GND") (pinfunction "GND_GND") (pintype "bidirectional"))
      (node (ref "R130") (pin "2") (pinfunction "2_2") (pintype "passive"))
      (node (ref "R7") (pin "1") (pinfunction "1_1") (pintype "passive"))
    )
    (net (code "3") (name "/AFE_AIN2") (class "Default")
      (node (ref "J7") (pin "1") (pinfunction "1_1") (pintype "passive"))
      (node (ref "J9") (pin "S") (pinfunction "OUT_S") (pintype "bidirectional"))
      (node (ref "R8") (pin "1") (pinfunction "1_1") (pintype "passive"))
    )
    (net (code "4") (name "/AFE_AIN3") (class "Default")
      (node (ref "J7") (pin "2") (pinfunction "2_2") (pintype "passive"))
      (node (ref "J9") (pin "GND") (pinfunction "GND_GND") (pintype "bidirectional"))
      (node (ref "R128") (pin "2") (pinfunction "2_2") (pintype "passive"))
      (node (ref "R9") (pin "1") (pinfunction "1_1") (pintype "passive"))
    )
    (net (code "5") (name "/AFE_~{DRDY}") (class "Default")
      (node (ref "R15") (pin "1") (pinfunction "1_1") (pintype "passive"))
      (node (ref "U4") (pin "21") (pinfunction "~{DRDY}_21") (pintype "output"))
    )
    (net (code "6") (name "/AFE_~{PWDN}") (class "Default")
      (node (ref "R18") (pin "1") (pinfunction "1_1") (pintype "passive"))
      (node (ref "U4") (pin "14") (pinfunction "~{SYNC}/~{PWDN}_14") (pintype "input"))
    )
    (net (code "7") (name "/AFE_~{RESET}") (class "Default")
      (node (ref "R17") (pin "1") (pinfunction "1_1") (pintype "passive"))
      (node (ref "U4") (pin "15") (pinfunction "~{RESET}_15") (pintype "input"))
    )
    (net (code "8") (name "/AIN0+") (class "Default")
      (node (ref "C25") (pin "1") (pinfunction "1_1") (pintype "passive"))
      (node (ref "J4") (pin "2") (pinfunction "2_2") (pintype "passive"))
      (node (ref "U8") (pin "3") (pinfunction "T+_3") (pintype "bidirectional"))
    )
    (net (code "9") (name "/AIN0-") (class "Default")
      (node (ref "C25") (pin "2") (pinfunction "2_2") (pintype "passive"))
      (node (ref "J4") (pin "1") (pinfunction "1_1") (pintype "passive"))
      (node (ref "U8") (pin "2") (pinfunction "T-_2") (pintype "bidirectional"))
    )
    (net (code "10") (name "/AIN1+") (class "Default")
      (node (ref "C28") (pin "1") (pinfunction "1_1") (pintype "passive"))
      (node (ref "J5") (pin "2") (pinfunction "2_2") (pintype "passive"))
      (node (ref "U7") (pin "3") (pinfunction "T+_3") (pintype "bidirectional"))
    )
    (net (code "11") (name "/AIN1-") (class "Default")
      (node (ref "C28") (pin "2") (pinfunction "2_2") (pintype "passive"))
      (node (ref "J5") (pin "1") (pinfunction "1_1") (pintype "passive"))
      (node (ref "U7") (pin "2") (pinfunction "T-_2") (pintype "bidirectional"))
    )
    (net (code "12") (name "/BT_CONN") (class "Default")
      (node (ref "R23") (pin "2") (pinfunction "2_2") (pintype "passive"))
      (node (ref "R45") (pin "2") (pinfunction "2_2") (pintype "passive"))
      (node (ref "U2") (pin "19") (pinfunction "PIO2_19") (pintype "bidirectional"))
    )
    (net (code "13") (name "/BT_RESET") (class "Default")
      (node (ref "R19") (pin "2") (pinfunction "2_2") (pintype "passive"))
      (node (ref "R44") (pin "1") (pinfunction "1_1") (pintype "passive"))
      (node (ref "U2") (pin "5") (pinfunction "RESET_5") (pintype "bidirectional"))
    )
    (net (code "14") (name "/BT_RXTX") (class "Default")
      (node (ref "R24") (pin "2") (pinfunction "2_2") (pintype "passive"))
      (node (ref "R47") (pin "2") (pinfunction "2_2") (pintype "passive"))
      (node (ref "U2") (pin "31") (pinfunction "PIO8_31") (pintype "bidirectional"))
    )
    (net (code "15") (name "/BT_STATE") (class "Default")
      (node (ref "R20") (pin "2") (pinfunction "2_2") (pintype "passive"))
      (node (ref "R46") (pin "2") (pinfunction "2_2") (pintype "passive"))
      (node (ref "U2") (pin "21") (pinfunction "PIO5_21") (pintype "bidirectional"))
    )
    (net (code "16") (name "/CS_AFE") (class "Default")
      (node (ref "R16") (pin "1") (pinfunction "1_1") (pintype "passive"))
      (node (ref "U4") (pin "20") (pinfunction "~{CS}_20") (pintype "input"))
    )
    (net (code "17") (name "/CS_DAC") (class "Default")
      (node (ref "R120") (pin "1") (pinfunction "1_1") (pintype "passive"))
      (node (ref "R5") (pin "1") (pinfunction "1_1") (pintype "passive"))
    )
    (net (code "18") (name "/CS_SD") (class "Default")
      (node (ref "R25") (pin "2") (pinfunction "2_2") (pintype "passive"))
      (node (ref "U$1") (pin "2") (pinfunction "CS_2") (pintype "input"))
    )
    (net (code "19") (name "/CS_TC0") (class "Default")
      (node (ref "R27") (pin "2") (pinfunction "2_2") (pintype "passive"))
      (node (ref "R91") (pin "1") (pinfunction "1_1") (pintype "passive"))
    )
    (net (code "20") (name "/CS_TC1") (class "Default")
      (node (ref "R28") (pin "2") (pinfunction "2_2") (pintype "passive"))
      (node (ref "R94") (pin "1") (pinfunction "1_1") (pintype "passive"))
    )
    (net (code "21") (name "/DAC0") (class "Default")
      (node (ref "J10") (pin "S") (pinfunction "OUT_S") (pintype "bidirectional"))
      (node (ref "U9") (pin "1") (pinfunction "VOUTA_1") (pintype "output"))
    )
    (net (code "22") (name "/DAC1") (class "Default")
      (node (ref "J11") (pin "S") (pinfunction "OUT_S") (pintype "bidirectional"))
      (node (ref "U9") (pin "2") (pinfunction "VOUTB_2") (pintype "output"))
    )
    (net (code "23") (name "/DAC_~{CLR}") (class "Default")
      (node (ref "R14") (pin "1") (pinfunction "1_1") (pintype "passive"))
      (node (ref "U9") (pin "5") (pinfunction "~{CLR}_5") (pintype "input"))
    )
    (net (code "24") (name "/DAC_~{LDAC}") (class "Default")
      (node (ref "R13") (pin "1") (pinfunction "1_1") (pintype "passive"))
      (node (ref "U9") (pin "4") (pinfunction "~{LDAC}_4") (pintype "input"))
    )
    (net (code "25") (name "/LED0") (class "Default")
      (node (ref "R98") (pin "2") (pinfunction "2_2") (pintype "passive"))
      (node (ref "U1") (pin "11") (pinfunction "P$11_11") (pintype "bidirectional"))
    )
    (net (code "26") (name "/LED1") (class "Default")
      (node (ref "R99") (pin "2") (pinfunction "2_2") (pintype "passive"))
      (node (ref "U1") (pin "12") (pinfunction "P$12_12") (pintype "bidirectional"))
    )
    (net (code "27") (name "/MICRO_~{RESET}") (class "Default")
      (node (ref "C29") (pin "1") (pinfunction "1_1") (pintype "passive"))
      (node (ref "R1") (pin "1") (pinfunction "1_1") (pintype "passive"))
      (node (ref "R100") (pin "1") (pinfunction "1_1") (pintype "passive"))
      (node (ref "S2") (pin "P$2") (pinfunction "2_P$2") (pintype "passive"))
    )
    (net (code "28") (name "/MISO") (class "Default")
      (node (ref "R57") (pin "2") (pinfunction "2_2") (pintype "passive"))
      (node (ref "R84") (pin "1") (pinfunction "1_1") (pintype "passive"))
      (node (ref "R92") (pin "1") (pinfunction "1_1") (pintype "passive"))
      (node (ref "R95") (pin "1") (pinfunction "1_1") (pintype "passive"))
      (node (ref "U1") (pin "6") (pinfunction "P$6_6") (pintype "bidirectional"))
    )
    (net (code "29") (name "/MOSI") (class "Default")
      (node (ref "R119") (pin "1") (pinfunction "1_1") (pintype "passive"))
      (node (ref "R56") (pin "2") (pinfunction "2_2") (pintype "passive"))
      (node (ref "R85") (pin "1") (pinfunction "1_1") (pintype "passive"))
      (node (ref "U1") (pin "5") (pinfunction "P$5_5") (pintype "bidirectional"))
    )
    (net (code "30") (name "/RTC_SQW") (class "Default")
      (node (ref "R12") (pin "1") (pinfunction "1_1") (pintype "passive"))
      (node (ref "R76") (pin "1") (pinfunction "1_1") (pintype "passive"))
      (node (ref "U3") (pin "7") (pinfunction "SQW_7") (pintype "bidirectional"))
    )
    (net (code "31") (name "/SCK") (class "Default")
      (node (ref "R118") (pin "1") (pinfunction "1_1") (pintype "passive"))
      (node (ref "R55") (pin "2") (pinfunction "2_2") (pintype "passive"))
      (node (ref "R86") (pin "1") (pinfunction "1_1") (pintype "passive"))
      (node (ref "R90") (pin "1") (pinfunction "1_1") (pintype "passive"))
      (node (ref "R93") (pin "1") (pinfunction "1_1") (pintype "passive"))
      (node (ref "U1") (pin "7") (pinfunction "P$7_7") (pintype "bidirectional"))
    )
    (net (code "32") (name "/SCL") (class "Default")
      (node (ref "R52") (pin "2") (pinfunction "2_2") (pintype "passive"))
      (node (ref "R81") (pin "2") (pinfunction "2_2") (pintype "passive"))
      (node (ref "U1") (pin "10") (pinfunction "P$10_10") (pintype "bidirectional"))
    )
    (net (code "33") (name "/SDA") (class "Default")
      (node (ref "R51") (pin "2") (pinfunction "2_2") (pintype "passive"))
      (node (ref "R82") (pin "2") (pinfunction "2_2") (pintype "passive"))
      (node (ref "U1") (pin "9") (pinfunction "P$9_9") (pintype "bidirectional"))
    )
    (net (code "34") (name "/SD_CD") (class "Default")
      (node (ref "R26") (pin "2") (pinfunction "2_2") (pintype "passive"))
      (node (ref "U$1") (pin "CD1") (pinfunction "CARD_DETECT_CD1") (pintype "passive"))
    )
    (net (code "35") (name "/SW2") (class "Default")
      (node (ref "C30") (pin "1") (pinfunction "1_1") (pintype "passive"))
      (node (ref "R101") (pin "1") (pinfunction "1_1") (pintype "passive"))
      (node (ref "S3") (pin "P$2") (pinfunction "2_P$2") (pintype "passive"))
      (node (ref "U1") (pin "13") (pinfunction "P$13_13") (pintype "bidirectional"))
    )
    (net (code "36") (name "/UART_RX") (class "Default")
      (node (ref "R22") (pin "2") (pinfunction "2_2") (pintype "passive"))
      (node (ref "U2") (pin "13") (pinfunction "UARTRX_13") (pintype "bidirectional"))
    )
    (net (code "37") (name "/UART_TX") (class "Default")
      (node (ref "R21") (pin "2") (pinfunction "2_2") (pintype "passive"))
      (node (ref "U2") (pin "14") (pinfunction "UARTTX_14") (pintype "bidirectional"))
    )
    (net (code "38") (name "/USB_N") (class "Default")
      (node (ref "R3") (pin "1") (pinfunction "1_1") (pintype "passive"))
      (node (ref "U1") (pin "32") (pinfunction "P$32_32") (pintype "bidirectional"))
    )
    (net (code "39") (name "/USB_P") (class "Default")
      (node (ref "R2") (pin "1") (pinfunction "1_1") (pintype "passive"))
      (node (ref "U1") (pin "31") (pinfunction "P$31_31") (pintype "bidirectional"))
    )
    (net (code "40") (name "/VBATT") (class "Default")
      (node (ref "C32") (pin "2") (pinfunction "2_2") (pintype "passive"))
      (node (ref "C9") (pin "2") (pinfunction "2_2") (pintype "passive"))
      (node (ref "CN1") (pin "1") (pinfunction "2_1") (pintype "passive"))
      (node (ref "U10") (pin "P$20") (pinfunction "BATT_P$20") (pintype "power_in"))
      (node (ref "U10") (pin "P$21") (pinfunction "BATT_P$21") (pintype "power_in"))
    )
    (net (code "41") (name "/VIN") (class "Default")
      (node (ref "C31") (pin "2") (pinfunction "2_2") (pintype "passive"))
      (node (ref "C34") (pin "2") (pinfunction "2_2") (pintype "passive"))
      (node (ref "C57") (pin "1") (pinfunction "1_1") (pintype "passive"))
      (node (ref "C58") (pin "1") (pinfunction "1_1") (pintype "passive"))
      (node (ref "J1") (pin "PWR") (pinfunction "PWR_PWR") (pintype "bidirectional"))
      (node (ref "U10") (pin "P$2") (pinfunction "DC_P$2") (pintype "power_in"))
      (node (ref "U10") (pin "P$3") (pinfunction "DC_P$3") (pintype "power_in"))
    )
    (net (code "42") (name "/VLDO") (class "Default")
      (node (ref "C6") (pin "2") (pinfunction "2_2") (pintype "passive"))
      (node (ref "R110") (pin "2") (pinfunction "2_2") (pintype "passive"))
      (node (ref "R111") (pin "2") (pinfunction "2_2") (pintype "passive"))
      (node (ref "R112") (pin "2") (pinfunction "2_2") (pintype "passive"))
      (node (ref "R113") (pin "2") (pinfunction "2_2") (pintype "passive"))
      (node (ref "R114") (pin "2") (pinfunction "2_2") (pintype "passive"))
      (node (ref "R115") (pin "2") (pinfunction "2_2") (pintype "passive"))
      (node (ref "U10") (pin "P$17") (pinfunction "LDO_P$17") (pintype "power_in"))
    )
    (net (code "43") (name "/VREF_2V5") (class "Default")
      (node (ref "C16") (pin "1") (pinfunction "1_1") (pintype "passive"))
      (node (ref "C17") (pin "1") (pinfunction "1_1") (pintype "passive"))
      (node (ref "R73") (pin "1") (pinfunction "1_1") (pintype "passive"))
      (node (ref "U6") (pin "5") (pinfunction "VOUT_5") (pintype "bidirectional"))
    )
    (net (code "44") (name "/VSYS") (class "Default")
      (node (ref "C41") (pin "1") (pinfunction "1_1") (pintype "passive"))
      (node (ref "C42") (pin "1") (pinfunction "1_1") (pintype "passive"))
      (node (ref "C47") (pin "1") (pinfunction "1_1") (pintype "passive"))
      (node (ref "C48") (pin "1") (pinfunction "1_1") (pintype "passive"))
      (node (ref "C56") (pin "1") (pinfunction "1_1") (pintype "passive"))
      (node (ref "C7") (pin "2") (pinfunction "2_2") (pintype "passive"))
      (node (ref "C8") (pin "2") (pinfunction "2_2") (pintype "passive"))
      (node (ref "JP1") (pin "2") (pinfunction "2_2") (pintype "passive"))
      (node (ref "R11") (pin "1") (pinfunction "1_1") (pintype "passive"))
      (node (ref "U10") (pin "P$23") (pinfunction "SYS_P$23") (pintype "power_in"))
      (node (ref "U10") (pin "P$24") (pinfunction "SYS_P$24") (pintype "power_in"))
      (node (ref "U11") (pin "4") (pinfunction "IN_4") (pintype "power_in"))
      (node (ref "U11") (pin "8") (pinfunction "~{SHDN}_8") (pintype "input"))
      (node (ref "U12") (pin "4") (pinfunction "IN_4") (pintype "power_in"))
      (node (ref "U12") (pin "8") (pinfunction "~{SHDN}_8") (pintype "input"))
    )
    (net (code "45") (name "/VUSB") (class "Default")
      (node (ref "C33") (pin "2") (pinfunction "2_2") (pintype "passive"))
      (node (ref "C35") (pin "2") (pinfunction "2_2") (pintype "passive"))
      (node (ref "R4") (pin "1") (pinfunction "1_1") (pintype "passive"))
      (node (ref "U1") (pin "39") (pinfunction "P$39_39") (pintype "bidirectional"))
      (node (ref "U10") (pin "P$18") (pinfunction "USB_P$18") (pintype "power_in"))
      (node (ref "U10") (pin "P$19") (pinfunction "USB_P$19") (pintype "power_in"))
    )
    (net (code "46") (name "3.3V") (class "Default")
      (node (ref "C10") (pin "1") (pinfunction "1_1") (pintype "passive"))
      (node (ref "C12") (pin "2") (pinfunction "2_2") (pintype "passive"))
      (node (ref "C14") (pin "2") (pinfunction "2_2") (pintype "passive"))
      (node (ref "C21") (pin "2") (pinfunction "2_2") (pintype "passive"))
      (node (ref "C22") (pin "1") (pinfunction "1_1") (pintype "passive"))
      (node (ref "C23") (pin "2") (pinfunction "2_2") (pintype "passive"))
      (node (ref "C24") (pin "2") (pinfunction "2_2") (pintype "passive"))
      (node (ref "C26") (pin "2") (pinfunction "2_2") (pintype "passive"))
      (node (ref "C27") (pin "2") (pinfunction "2_2") (pintype "passive"))
      (node (ref "C4") (pin "2") (pinfunction "2_2") (pintype "passive"))
      (node (ref "C45") (pin "2") (pinfunction "2_2") (pintype "passive"))
      (node (ref "C46") (pin "2") (pinfunction "2_2") (pintype "passive"))
      (node (ref "C5") (pin "2") (pinfunction "2_2") (pintype "passive"))
      (node (ref "C53") (pin "A") (pinfunction "+_A") (pintype "passive"))
      (node (ref "R100") (pin "2") (pinfunction "2_2") (pintype "passive"))
      (node (ref "R101") (pin "2") (pinfunction "2_2") (pintype "passive"))
      (node (ref "R117") (pin "1") (pinfunction "1_1") (pintype "passive"))
      (node (ref "R44") (pin "2") (pinfunction "2_2") (pintype "passive"))
      (node (ref "R49") (pin "2") (pinfunction "2_2") (pintype "passive"))
      (node (ref "R50") (pin "2") (pinfunction "2_2") (pintype "passive"))
      (node (ref "R76") (pin "2") (pinfunction "2_2") (pintype "passive"))
      (node (ref "R77") (pin "2") (pinfunction "2_2") (pintype "passive"))
      (node (ref "R78") (pin "2") (pinfunction "2_2") (pintype "passive"))
      (node (ref "R79") (pin "2") (pinfunction "2_2") (pintype "passive"))
      (node (ref "U$1") (pin "4") (pinfunction "VDD_4") (pintype "power_in"))
      (node (ref "U12") (pin "5") (pinfunction "OUT_5") (pintype "power_in"))
      (node (ref "U12") (pin "6") (pinfunction "SENSE_6") (pintype "passive"))
      (node (ref "U2") (pin "11") (pinfunction "VDD_11") (pintype "bidirectional"))
      (node (ref "U3") (pin "8") (pinfunction "VCC_8") (pintype "power_in"))
      (node (ref "U4") (pin "16") (pinfunction "DVDD_16") (pintype "power_in"))
      (node (ref "U5") (pin "5") (pinfunction "VDD_5") (pintype "power_in"))
      (node (ref "U7") (pin "4") (pinfunction "VDD_4") (pintype "bidirectional"))
      (node (ref "U8") (pin "4") (pinfunction "VDD_4") (pintype "bidirectional"))
    )
    (net (code "47") (name "5V") (class "Default")
      (node (ref "C11") (pin "2") (pinfunction "2_2") (pintype "passive"))
      (node (ref "C13") (pin "2") (pinfunction "2_2") (pintype "passive"))
      (node (ref "C15") (pin "1") (pinfunction "1_1") (pintype "passive"))
      (node (ref "C18") (pin "1") (pinfunction "1_1") (pintype "passive"))
      (node (ref "C43") (pin "2") (pinfunction "2_2") (pintype "passive"))
      (node (ref "C44") (pin "2") (pinfunction "2_2") (pintype "passive"))
      (node (ref "C49") (pin "2") (pinfunction "2_2") (pintype "passive"))
      (node (ref "C51") (pin "2") (pinfunction "2_2") (pintype "passive"))
      (node (ref "C55") (pin "A") (pinfunction "+_A") (pintype "passive"))
      (node (ref "R116") (pin "1") (pinfunction "1_1") (pintype "passive"))
      (node (ref "R75") (pin "2") (pinfunction "2_2") (pintype "passive"))
      (node (ref "U11") (pin "5") (pinfunction "OUT_5") (pintype "power_in"))
      (node (ref "U11") (pin "6") (pinfunction "SENSE_6") (pintype "passive"))
      (node (ref "U4") (pin "1") (pinfunction "AVDD_1") (pintype "power_in"))
      (node (ref "U6") (pin "4") (pinfunction "VIN_4") (pintype "bidirectional"))
      (node (ref "U9") (pin "9") (pinfunction "VDD_9") (pintype "power_in"))
    )
    (net (code "48") (name "GND") (class "Default")
      (node (ref "C1") (pin "1") (pinfunction "1_1") (pintype "passive"))
      (node (ref "C10") (pin "2") (pinfunction "2_2") (pintype "passive"))
      (node (ref "C11") (pin "1") (pinfunction "1_1") (pintype "passive"))
      (node (ref "C12") (pin "1") (pinfunction "1_1") (pintype "passive"))
      (node (ref "C13") (pin "1") (pinfunction "1_1") (pintype "passive"))
      (node (ref "C14") (pin "1") (pinfunction "1_1") (pintype "passive"))
      (node (ref "C15") (pin "2") (pinfunction "2_2") (pintype "passive"))
      (node (ref "C16") (pin "2") (pinfunction "2_2") (pintype "passive"))
      (node (ref "C17") (pin "2") (pinfunction "2_2") (pintype "passive"))
      (node (ref "C18") (pin "2") (pinfunction "2_2") (pintype "passive"))
      (node (ref "C19") (pin "2") (pinfunction "2_2") (pintype "passive"))
      (node (ref "C2") (pin "1") (pinfunction "1_1") (pintype "passive"))
      (node (ref "C20") (pin "2") (pinfunction "2_2") (pintype "passive"))
      (node (ref "C21") (pin "1") (pinfunction "1_1") (pintype "passive"))
      (node (ref "C22") (pin "2") (pinfunction "2_2") (pintype "passive"))
      (node (ref "C23") (pin "1") (pinfunction "1_1") (pintype "passive"))
      (node (ref "C24") (pin "1") (pinfunction "1_1") (pintype "passive"))
      (node (ref "C26") (pin "1") (pinfunction "1_1") (pintype "passive"))
      (node (ref "C27") (pin "1") (pinfunction "1_1") (pintype "passive"))
      (node (ref "C29") (pin "2") (pinfunction "2_2") (pintype "passive"))
      (node (ref "C30") (pin "2") (pinfunction "2_2") (pintype "passive"))
      (node (ref "C31") (pin "1") (pinfunction "1_1") (pintype "passive"))
      (node (ref "C32") (pin "1") (pinfunction "1_1") (pintype "passive"))
      (node (ref "C33") (pin "1") (pinfunction "1_1") (pintype "passive"))
      (node (ref "C34") (pin "1") (pinfunction "1_1") (pintype "passive"))
      (node (ref "C35") (pin "1") (pinfunction "1_1") (pintype "passive"))
      (node (ref "C37") (pin "2") (pinfunction "2_2") (pintype "passive"))
      (node (ref "C38") (pin "2") (pinfunction "2_2") (pintype "passive"))
      (node (ref "C39") (pin "2") (pinfunction "2_2") (pintype "passive"))
      (node (ref "C4") (pin "1") (pinfunction "1_1") (pintype "passive"))
      (node (ref "C40") (pin "2") (pinfunction "2_2") (pintype "passive"))
      (node (ref "C41") (pin "2") (pinfunction "2_2") (pintype "passive"))
      (node (ref "C42") (pin "2") (pinfunction "2_2") (pintype "passive"))
      (node (ref "C43") (pin "1") (pinfunction "1_1") (pintype "passive"))
      (node (ref "C44") (pin "1") (pinfunction "1_1") (pintype "passive"))
      (node (ref "C45") (pin "1") (pinfunction "1_1") (pintype "passive"))
      (node (ref "C46") (pin "1") (pinfunction "1_1") (pintype "passive"))
      (node (ref "C47") (pin "2") (pinfunction "2_2") (pintype "passive"))
      (node (ref "C48") (pin "2") (pinfunction "2_2") (pintype "passive"))
      (node (ref "C49") (pin "1") (pinfunction "1_1") (pintype "passive"))
      (node (ref "C5") (pin "1") (pinfunction "1_1") (pintype "passive"))
      (node (ref "C50") (pin "2") (pinfunction "2_2") (pintype "passive"))
      (node (ref "C51") (pin "1") (pinfunction "1_1") (pintype "passive"))
      (node (ref "C52") (pin "2") (pinfunction "2_2") (pintype "passive"))
      (node (ref "C53") (pin "C") (pinfunction "-_C") (pintype "passive"))
      (node (ref "C54") (pin "2") (pinfunction "2_2") (pintype "passive"))
      (node (ref "C55") (pin "C") (pinfunction "-_C") (pintype "passive"))
      (node (ref "C56") (pin "2") (pinfunction "2_2") (pintype "passive"))
      (node (ref "C57") (pin "2") (pinfunction "2_2") (pintype "passive"))
      (node (ref "C58") (pin "2") (pinfunction "2_2") (pintype "passive"))
      (node (ref "C6") (pin "1") (pinfunction "1_1") (pintype "passive"))
      (node (ref "C7") (pin "1") (pinfunction "1_1") (pintype "passive"))
      (node (ref "C8") (pin "1") (pinfunction "1_1") (pintype "passive"))
      (node (ref "C9") (pin "1") (pinfunction "1_1") (pintype "passive"))
      (node (ref "CN1") (pin "2") (pinfunction "1_2") (pintype "passive"))
      (node (ref "D1") (pin "C") (pinfunction "C_C") (pintype "passive"))
      (node (ref "D2") (pin "C") (pinfunction "C_C") (pintype "passive"))
      (node (ref "D3") (pin "C") (pinfunction "C_C") (pintype "passive"))
      (node (ref "J1") (pin "GND") (pinfunction "GND_GND") (pintype "bidirectional"))
      (node (ref "J1") (pin "GNDBREAK") (pinfunction "GNDBREAK_GNDBREAK") (pintype "bidirectional"))
      (node (ref "J10") (pin "GND") (pinfunction "GND_GND") (pintype "bidirectional"))
      (node (ref "J11") (pin "GND") (pinfunction "GND_GND") (pintype "bidirectional"))
      (node (ref "J2") (pin "GND") (pinfunction "GND_GND") (pintype "bidirectional"))
      (node (ref "JP1") (pin "1") (pinfunction "1_1") (pintype "passive"))
      (node (ref "LED3") (pin "P$3") (pinfunction "GC_P$3") (pintype "passive"))
      (node (ref "LED3") (pin "P$4") (pinfunction "RC_P$4") (pintype "passive"))
      (node (ref "PAD1") (pin "1") (pinfunction "P_1") (pintype "passive"))
      (node (ref "PAD2") (pin "1") (pinfunction "P_1") (pintype "passive"))
      (node (ref "R102") (pin "1") (pinfunction "1_1") (pintype "passive"))
      (node (ref "R104") (pin "1") (pinfunction "1_1") (pintype "passive"))
      (node (ref "R105") (pin "1") (pinfunction "1_1") (pintype "passive"))
      (node (ref "R106") (pin "1") (pinfunction "1_1") (pintype "passive"))
      (node (ref "R107") (pin "1") (pinfunction "1_1") (pintype "passive"))
      (node (ref "R108") (pin "1") (pinfunction "1_1") (pintype "passive"))
      (node (ref "R109") (pin "1") (pinfunction "1_1") (pintype "passive"))
      (node (ref "R128") (pin "1") (pinfunction "1_1") (pintype "passive"))
      (node (ref "R130") (pin "1") (pinfunction "1_1") (pintype "passive"))
      (node (ref "R33") (pin "1") (pinfunction "1_1") (pintype "passive"))
      (node (ref "R34") (pin "1") (pinfunction "1_1") (pintype "passive"))
      (node (ref "R39") (pin "1") (pinfunction "1_1") (pintype "passive"))
      (node (ref "R48") (pin "1") (pinfunction "1_1") (pintype "passive"))
      (node (ref "S2") (pin "P$1") (pinfunction "1_P$1") (pintype "passive"))
      (node (ref "S3") (pin "P$1") (pinfunction "1_P$1") (pintype "passive"))
      (node (ref "U$1") (pin "6") (pinfunction "VSS_6") (pintype "power_in"))
      (node (ref "U$1") (pin "MT1") (pinfunction "GND_MT1") (pintype "power_in"))
      (node (ref "U$1") (pin "MT2") (pinfunction "GND1_MT2") (pintype "power_in"))
      (node (ref "U1") (pin "1") (pinfunction "P$1_1") (pintype "bidirectional"))
      (node (ref "U10") (pin "P$13") (pinfunction "GND_P$13") (pintype "power_in"))
      (node (ref "U10") (pin "P$29") (pinfunction "EP_P$29") (pintype "power_in"))
      (node (ref "U10") (pin "P$9") (pinfunction "GND_P$9") (pintype "power_in"))
      (node (ref "U11") (pin "3") (pinfunction "GND_3") (pintype "power_in"))
      (node (ref "U12") (pin "3") (pinfunction "GND_3") (pintype "power_in"))
      (node (ref "U2") (pin "1") (pinfunction "GND_1") (pintype "bidirectional"))
      (node (ref "U2") (pin "12") (pinfunction "GND1_12") (pintype "bidirectional"))
      (node (ref "U2") (pin "28") (pinfunction "GND2_28") (pintype "bidirectional"))
      (node (ref "U2") (pin "29") (pinfunction "GND3_29") (pintype "bidirectional"))
      (node (ref "U3") (pin "4") (pinfunction "GND_4") (pintype "power_in"))
      (node (ref "U4") (pin "17") (pinfunction "DGND_17") (pintype "power_in"))
      (node (ref "U4") (pin "2") (pinfunction "AGND_2") (pintype "power_in"))
      (node (ref "U4") (pin "3") (pinfunction "VREFN_3") (pintype "passive"))
      (node (ref "U4") (pin "5") (pinfunction "AINCOM_5") (pintype "input"))
      (node (ref "U5") (pin "2") (pinfunction "GND_2") (pintype "power_in"))
      (node (ref "U5") (pin "DAP") (pinfunction "DAP_DAP") (pintype "bidirectional"))
      (node (ref "U6") (pin "2") (pinfunction "GND_2") (pintype "bidirectional"))
      (node (ref "U7") (pin "1") (pinfunction "VSS_1") (pintype "bidirectional"))
      (node (ref "U8") (pin "1") (pinfunction "VSS_1") (pintype "bidirectional"))
      (node (ref "U9") (pin "3") (pinfunction "GND_3") (pintype "power_in"))
    )
    (net (code "49") (name "Net-(D1-PadA)") (class "Default")
      (node (ref "D1") (pin "A") (pinfunction "A_A") (pintype "passive"))
      (node (ref "R45") (pin "1") (pinfunction "1_1") (pintype "passive"))
    )
    (net (code "50") (name "Net-(D2-PadA)") (class "Default")
      (node (ref "D2") (pin "A") (pinfunction "A_A") (pintype "passive"))
      (node (ref "R46") (pin "1") (pinfunction "1_1") (pintype "passive"))
    )
    (net (code "51") (name "Net-(D3-PadA)") (class "Default")
      (node (ref "D3") (pin "A") (pinfunction "A_A") (pintype "passive"))
      (node (ref "R47") (pin "1") (pinfunction "1_1") (pintype "passive"))
    )
    (net (code "52") (name "Net-(J2-PadD+)") (class "Default")
      (node (ref "J2") (pin "D+") (pinfunction "D+_D+") (pintype "bidirectional"))
      (node (ref "R2") (pin "2") (pinfunction "2_2") (pintype "passive"))
    )
    (net (code "53") (name "Net-(J2-PadD-)") (class "Default")
      (node (ref "J2") (pin "D-") (pinfunction "D-_D-") (pintype "bidirectional"))
      (node (ref "R3") (pin "2") (pinfunction "2_2") (pintype "passive"))
    )
    (net (code "54") (name "Net-(J2-PadVBUS)") (class "Default")
      (node (ref "J2") (pin "VBUS") (pinfunction "VBUS_VBUS") (pintype "bidirectional"))
      (node (ref "R4") (pin "2") (pinfunction "2_2") (pintype "passive"))
    )
    (net (code "55") (name "Net-(LED3-GA)") (class "Default")
      (node (ref "LED3") (pin "P$1") (pinfunction "GA_P$1") (pintype "passive"))
      (node (ref "R99") (pin "1") (pinfunction "1_1") (pintype "passive"))
    )
    (net (code "56") (name "Net-(LED3-RA)") (class "Default")
      (node (ref "LED3") (pin "P$2") (pinfunction "RA_P$2") (pintype "passive"))
      (node (ref "R98") (pin "1") (pinfunction "1_1") (pintype "passive"))
    )
    (net (code "57") (name "Net-(U$1-DATA_IN)") (class "Default")
      (node (ref "R85") (pin "2") (pinfunction "2_2") (pintype "passive"))
      (node (ref "U$1") (pin "3") (pinfunction "DATA_IN_3") (pintype "input"))
    )
    (net (code "58") (name "Net-(U$1-DATA_OUT)") (class "Default")
      (node (ref "R84") (pin "2") (pinfunction "2_2") (pintype "passive"))
      (node (ref "U$1") (pin "7") (pinfunction "DATA_OUT_7") (pintype "output"))
    )
    (net (code "59") (name "Net-(U$1-SCLK)") (class "Default")
      (node (ref "R86") (pin "2") (pinfunction "2_2") (pintype "passive"))
      (node (ref "U$1") (pin "5") (pinfunction "SCLK_5") (pintype "input"))
    )
    (net (code "60") (name "Net-(U1-P$2)") (class "Default")
      (node (ref "C1") (pin "2") (pinfunction "2_2") (pintype "passive"))
      (node (ref "C2") (pin "2") (pinfunction "2_2") (pintype "passive"))
      (node (ref "R11") (pin "2") (pinfunction "2_2") (pintype "passive"))
      (node (ref "U1") (pin "2") (pinfunction "P$2_2") (pintype "bidirectional"))
    )
    (net (code "61") (name "Net-(U1-P$4)") (class "Default")
      (node (ref "R1") (pin "2") (pinfunction "2_2") (pintype "passive"))
      (node (ref "U1") (pin "4") (pinfunction "P$4_4") (pintype "bidirectional"))
    )
    (net (code "62") (name "Net-(U1-P$8)") (class "Default")
      (node (ref "R5") (pin "2") (pinfunction "2_2") (pintype "passive"))
      (node (ref "U1") (pin "8") (pinfunction "P$8_8") (pintype "bidirectional"))
    )
    (net (code "63") (name "Net-(U1-P$14)") (class "Default")
      (node (ref "R12") (pin "2") (pinfunction "2_2") (pintype "passive"))
      (node (ref "U1") (pin "14") (pinfunction "P$14_14") (pintype "bidirectional"))
    )
    (net (code "64") (name "Net-(U1-P$15)") (class "Default")
      (node (ref "R13") (pin "2") (pinfunction "2_2") (pintype "passive"))
      (node (ref "U1") (pin "15") (pinfunction "P$15_15") (pintype "bidirectional"))
    )
    (net (code "65") (name "Net-(U1-P$16)") (class "Default")
      (node (ref "R14") (pin "2") (pinfunction "2_2") (pintype "passive"))
      (node (ref "U1") (pin "16") (pinfunction "P$16_16") (pintype "bidirectional"))
    )
    (net (code "66") (name "Net-(U1-P$17)") (class "Default")
      (node (ref "R15") (pin "2") (pinfunction "2_2") (pintype "passive"))
      (node (ref "U1") (pin "17") (pinfunction "P$17_17") (pintype "bidirectional"))
    )
    (net (code "67") (name "Net-(U1-P$18)") (class "Default")
      (node (ref "R16") (pin "2") (pinfunction "2_2") (pintype "passive"))
      (node (ref "U1") (pin "18") (pinfunction "P$18_18") (pintype "bidirectional"))
    )
    (net (code "68") (name "Net-(U1-P$19)") (class "Default")
      (node (ref "R17") (pin "2") (pinfunction "2_2") (pintype "passive"))
      (node (ref "U1") (pin "19") (pinfunction "P$19_19") (pintype "bidirectional"))
    )
    (net (code "69") (name "Net-(U1-P$20)") (class "Default")
      (node (ref "R18") (pin "2") (pinfunction "2_2") (pintype "passive"))
      (node (ref "U1") (pin "20") (pinfunction "P$20_20") (pintype "bidirectional"))
    )
    (net (code "70") (name "Net-(U1-P$21)") (class "Default")
      (node (ref "R28") (pin "1") (pinfunction "1_1") (pintype "passive"))
      (node (ref "U1") (pin "21") (pinfunction "P$21_21") (pintype "bidirectional"))
    )
    (net (code "71") (name "Net-(U1-P$22)") (class "Default")
      (node (ref "R27") (pin "1") (pinfunction "1_1") (pintype "passive"))
      (node (ref "U1") (pin "22") (pinfunction "P$22_22") (pintype "bidirectional"))
    )
    (net (code "72") (name "Net-(U1-P$23)") (class "Default")
      (node (ref "R26") (pin "1") (pinfunction "1_1") (pintype "passive"))
      (node (ref "U1") (pin "23") (pinfunction "P$23_23") (pintype "bidirectional"))
    )
    (net (code "73") (name "Net-(U1-P$24)") (class "Default")
      (node (ref "R25") (pin "1") (pinfunction "1_1") (pintype "passive"))
      (node (ref "U1") (pin "24") (pinfunction "P$24_24") (pintype "bidirectional"))
    )
    (net (code "74") (name "Net-(U1-P$25)") (class "Default")
      (node (ref "R24") (pin "1") (pinfunction "1_1") (pintype "passive"))
      (node (ref "U1") (pin "25") (pinfunction "P$25_25") (pintype "bidirectional"))
    )
    (net (code "75") (name "Net-(U1-P$26)") (class "Default")
      (node (ref "R23") (pin "1") (pinfunction "1_1") (pintype "passive"))
      (node (ref "U1") (pin "26") (pinfunction "P$26_26") (pintype "bidirectional"))
    )
    (net (code "76") (name "Net-(U1-P$27)") (class "Default")
      (node (ref "R22") (pin "1") (pinfunction "1_1") (pintype "passive"))
      (node (ref "U1") (pin "27") (pinfunction "P$27_27") (pintype "bidirectional"))
    )
    (net (code "77") (name "Net-(U1-P$28)") (class "Default")
      (node (ref "R21") (pin "1") (pinfunction "1_1") (pintype "passive"))
      (node (ref "U1") (pin "28") (pinfunction "P$28_28") (pintype "bidirectional"))
    )
    (net (code "78") (name "Net-(U1-P$29)") (class "Default")
      (node (ref "R20") (pin "1") (pinfunction "1_1") (pintype "passive"))
      (node (ref "U1") (pin "29") (pinfunction "P$29_29") (pintype "bidirectional"))
    )
    (net (code "79") (name "Net-(U1-P$30)") (class "Default")
      (node (ref "R19") (pin "1") (pinfunction "1_1") (pintype "passive"))
      (node (ref "U1") (pin "30") (pinfunction "P$30_30") (pintype "bidirectional"))
    )
    (net (code "80") (name "Net-(U2-PIO3)") (class "Default")
      (node (ref "R39") (pin "2") (pinfunction "2_2") (pintype "passive"))
      (node (ref "U2") (pin "20") (pinfunction "PIO3_20") (pintype "bidirectional"))
    )
    (net (code "81") (name "Net-(U2-PIO6)") (class "Default")
      (node (ref "R33") (pin "2") (pinfunction "2_2") (pintype "passive"))
      (node (ref "U2") (pin "3") (pinfunction "PIO6_3") (pintype "bidirectional"))
    )
    (net (code "82") (name "Net-(U2-PIO7)") (class "Default")
      (node (ref "R34") (pin "2") (pinfunction "2_2") (pintype "passive"))
      (node (ref "U2") (pin "4") (pinfunction "PIO7_4") (pintype "bidirectional"))
    )
    (net (code "83") (name "Net-(U3-SCL)") (class "Default")
      (node (ref "R77") (pin "1") (pinfunction "1_1") (pintype "passive"))
      (node (ref "R81") (pin "1") (pinfunction "1_1") (pintype "passive"))
      (node (ref "U3") (pin "6") (pinfunction "SCL_6") (pintype "bidirectional"))
    )
    (net (code "84") (name "Net-(U3-SDA)") (class "Default")
      (node (ref "R78") (pin "1") (pinfunction "1_1") (pintype "passive"))
      (node (ref "R82") (pin "1") (pinfunction "1_1") (pintype "passive"))
      (node (ref "U3") (pin "5") (pinfunction "SDA_5") (pintype "bidirectional"))
    )
    (net (code "85") (name "Net-(U3-X1)") (class "Default")
      (node (ref "U3") (pin "1") (pinfunction "X1_1") (pintype "passive"))
      (node (ref "Y2") (pin "2") (pinfunction "2_2") (pintype "passive"))
    )
    (net (code "86") (name "Net-(U3-X2)") (class "Default")
      (node (ref "U3") (pin "2") (pinfunction "X2_2") (pintype "passive"))
      (node (ref "Y2") (pin "1") (pinfunction "1_1") (pintype "passive"))
    )
    (net (code "87") (name "Net-(U3-~{INTA})") (class "Default")
      (node (ref "R79") (pin "1") (pinfunction "1_1") (pintype "passive"))
      (node (ref "U3") (pin "3") (pinfunction "~{INTA}_3") (pintype "bidirectional"))
    )
    (net (code "88") (name "Net-(U4-AIN0)") (class "Default")
      (node (ref "C3") (pin "2") (pinfunction "2_2") (pintype "passive"))
      (node (ref "C52") (pin "1") (pinfunction "1_1") (pintype "passive"))
      (node (ref "R6") (pin "2") (pinfunction "2_2") (pintype "passive"))
      (node (ref "U4") (pin "6") (pinfunction "AIN0_6") (pintype "input"))
    )
    (net (code "89") (name "Net-(U4-AIN1)") (class "Default")
      (node (ref "C3") (pin "1") (pinfunction "1_1") (pintype "passive"))
      (node (ref "R7") (pin "2") (pinfunction "2_2") (pintype "passive"))
      (node (ref "U4") (pin "7") (pinfunction "AIN1_7") (pintype "input"))
    )
    (net (code "90") (name "Net-(U4-AIN2)") (class "Default")
      (node (ref "C36") (pin "2") (pinfunction "2_2") (pintype "passive"))
      (node (ref "C54") (pin "1") (pinfunction "1_1") (pintype "passive"))
      (node (ref "R8") (pin "2") (pinfunction "2_2") (pintype "passive"))
      (node (ref "U4") (pin "8") (pinfunction "AIN2_8") (pintype "input"))
    )
    (net (code "91") (name "Net-(U4-AIN3)") (class "Default")
      (node (ref "C36") (pin "1") (pinfunction "1_1") (pintype "passive"))
      (node (ref "R9") (pin "2") (pinfunction "2_2") (pintype "passive"))
      (node (ref "U4") (pin "9") (pinfunction "AIN3_9") (pintype "input"))
    )
    (net (code "92") (name "Net-(U4-DIN)") (class "Default")
      (node (ref "R56") (pin "1") (pinfunction "1_1") (pintype "passive"))
      (node (ref "U4") (pin "23") (pinfunction "DIN_23") (pintype "bidirectional"))
    )
    (net (code "93") (name "Net-(U4-DOUT)") (class "Default")
      (node (ref "R57") (pin "1") (pinfunction "1_1") (pintype "passive"))
      (node (ref "U4") (pin "22") (pinfunction "DOUT_22") (pintype "output"))
    )
    (net (code "94") (name "Net-(U4-SCLK)") (class "Default")
      (node (ref "R55") (pin "1") (pinfunction "1_1") (pintype "passive"))
      (node (ref "U4") (pin "24") (pinfunction "SCLK_24") (pintype "bidirectional"))
    )
    (net (code "95") (name "Net-(U4-VREFP)") (class "Default")
      (node (ref "R73") (pin "2") (pinfunction "2_2") (pintype "passive"))
      (node (ref "U4") (pin "4") (pinfunction "VREFP_4") (pintype "passive"))
    )
    (net (code "96") (name "Net-(U4-XTAL1{slash}CLKIN)") (class "Default")
      (node (ref "C19") (pin "1") (pinfunction "1_1") (pintype "passive"))
      (node (ref "U4") (pin "19") (pinfunction "XTAL1/CLKIN_19") (pintype "input"))
      (node (ref "Y1") (pin "2") (pinfunction "2_2") (pintype "passive"))
    )
    (net (code "97") (name "Net-(U4-XTAL2)") (class "Default")
      (node (ref "C20") (pin "1") (pinfunction "1_1") (pintype "passive"))
      (node (ref "U4") (pin "18") (pinfunction "XTAL2_18") (pintype "input"))
      (node (ref "Y1") (pin "1") (pinfunction "1_1") (pintype "passive"))
    )
    (net (code "98") (name "Net-(U5-SCL)") (class "Default")
      (node (ref "R50") (pin "1") (pinfunction "1_1") (pintype "passive"))
      (node (ref "R52") (pin "1") (pinfunction "1_1") (pintype "passive"))
      (node (ref "U5") (pin "6") (pinfunction "SCL_6") (pintype "bidirectional"))
    )
    (net (code "99") (name "Net-(U5-SDA)") (class "Default")
      (node (ref "R49") (pin "1") (pinfunction "1_1") (pintype "passive"))
      (node (ref "R51") (pin "1") (pinfunction "1_1") (pintype "passive"))
      (node (ref "U5") (pin "1") (pinfunction "SDA_1") (pintype "bidirectional"))
    )
    (net (code "100") (name "Net-(U6-EN)") (class "Default")
      (node (ref "R75") (pin "1") (pinfunction "1_1") (pintype "passive"))
      (node (ref "U6") (pin "3") (pinfunction "EN_3") (pintype "bidirectional"))
    )
    (net (code "101") (name "Net-(U7-CS)") (class "Default")
      (node (ref "R94") (pin "2") (pinfunction "2_2") (pintype "passive"))
      (node (ref "U7") (pin "6") (pinfunction "CS_6") (pintype "bidirectional"))
    )
    (net (code "102") (name "Net-(U7-MISO)") (class "Default")
      (node (ref "R95") (pin "2") (pinfunction "2_2") (pintype "passive"))
      (node (ref "U7") (pin "7") (pinfunction "MISO_7") (pintype "bidirectional"))
    )
    (net (code "103") (name "Net-(U7-SCK)") (class "Default")
      (node (ref "R93") (pin "2") (pinfunction "2_2") (pintype "passive"))
      (node (ref "U7") (pin "5") (pinfunction "SCK_5") (pintype "bidirectional"))
    )
    (net (code "104") (name "Net-(U8-CS)") (class "Default")
      (node (ref "R91") (pin "2") (pinfunction "2_2") (pintype "passive"))
      (node (ref "U8") (pin "6") (pinfunction "CS_6") (pintype "bidirectional"))
    )
    (net (code "105") (name "Net-(U8-MISO)") (class "Default")
      (node (ref "R92") (pin "2") (pinfunction "2_2") (pintype "passive"))
      (node (ref "U8") (pin "7") (pinfunction "MISO_7") (pintype "bidirectional"))
    )
    (net (code "106") (name "Net-(U8-SCK)") (class "Default")
      (node (ref "R90") (pin "2") (pinfunction "2_2") (pintype "passive"))
      (node (ref "U8") (pin "5") (pinfunction "SCK_5") (pintype "bidirectional"))
    )
    (net (code "107") (name "Net-(U9-DIN)") (class "Default")
      (node (ref "R119") (pin "2") (pinfunction "2_2") (pintype "passive"))
      (node (ref "U9") (pin "8") (pinfunction "DIN_8") (pintype "input"))
    )
    (net (code "108") (name "Net-(U9-SCLK)") (class "Default")
      (node (ref "R118") (pin "2") (pinfunction "2_2") (pintype "passive"))
      (node (ref "U9") (pin "7") (pinfunction "SCLK_7") (pintype "bidirectional"))
    )
    (net (code "109") (name "Net-(U9-VREF_IO)") (class "Default")
      (node (ref "C50") (pin "1") (pinfunction "1_1") (pintype "passive"))
      (node (ref "U9") (pin "10") (pinfunction "VREF_IO_10") (pintype "bidirectional"))
    )
    (net (code "110") (name "Net-(U9-~{SYNC})") (class "Default")
      (node (ref "R120") (pin "2") (pinfunction "2_2") (pintype "passive"))
      (node (ref "U9") (pin "6") (pinfunction "~{SYNC}_6") (pintype "input"))
    )
    (net (code "111") (name "Net-(U10-CT)") (class "Default")
      (node (ref "C37") (pin "1") (pinfunction "1_1") (pintype "passive"))
      (node (ref "U10") (pin "P$10") (pinfunction "CT_P$10") (pintype "passive"))
    )
    (net (code "112") (name "Net-(U10-ISET)") (class "Default")
      (node (ref "R48") (pin "2") (pinfunction "2_2") (pintype "passive"))
      (node (ref "U10") (pin "P$11") (pinfunction "ISET_P$11") (pintype "passive"))
    )
    (net (code "113") (name "Net-(U10-PEN1)") (class "Default")
      (node (ref "R107") (pin "2") (pinfunction "2_2") (pintype "passive"))
      (node (ref "U10") (pin "P$5") (pinfunction "PEN1_P$5") (pintype "input"))
    )
    (net (code "114") (name "Net-(U10-PEN2)") (class "Default")
      (node (ref "R108") (pin "2") (pinfunction "2_2") (pintype "passive"))
      (node (ref "U10") (pin "P$6") (pinfunction "PEN2_P$6") (pintype "input"))
    )
    (net (code "115") (name "Net-(U10-PSET)") (class "Default")
      (node (ref "R102") (pin "2") (pinfunction "2_2") (pintype "passive"))
      (node (ref "U10") (pin "P$7") (pinfunction "PSET_P$7") (pintype "passive"))
    )
    (net (code "116") (name "Net-(U10-THM)") (class "Default")
      (node (ref "R103") (pin "1") (pinfunction "1_1") (pintype "passive"))
      (node (ref "R104") (pin "2") (pinfunction "2_2") (pintype "passive"))
      (node (ref "U10") (pin "P$14") (pinfunction "THM_P$14") (pintype "passive"))
    )
    (net (code "117") (name "Net-(U10-THMEN)") (class "Default")
      (node (ref "R105") (pin "2") (pinfunction "2_2") (pintype "passive"))
      (node (ref "U10") (pin "P$15") (pinfunction "THMEN_P$15") (pintype "input"))
    )
    (net (code "118") (name "Net-(U10-THMSW)") (class "Default")
      (node (ref "R103") (pin "2") (pinfunction "2_2") (pintype "passive"))
      (node (ref "U10") (pin "P$16") (pinfunction "THMSW_P$16") (pintype "passive"))
    )
    (net (code "119") (name "Net-(U10-USUS)") (class "Default")
      (node (ref "R106") (pin "2") (pinfunction "2_2") (pintype "passive"))
      (node (ref "U10") (pin "P$12") (pinfunction "USUS_P$12") (pintype "input"))
    )
    (net (code "120") (name "Net-(U10-VL)") (class "Default")
      (node (ref "C38") (pin "1") (pinfunction "1_1") (pintype "passive"))
      (node (ref "U10") (pin "P$8") (pinfunction "VL_P$8") (pintype "passive"))
    )
    (net (code "121") (name "Net-(U10-~{CEN})") (class "Default")
      (node (ref "R109") (pin "2") (pinfunction "2_2") (pintype "passive"))
      (node (ref "U10") (pin "P$4") (pinfunction "~{CEN}_P$4") (pintype "input"))
    )
    (net (code "122") (name "Net-(U10-~{CHG})") (class "Default")
      (node (ref "R110") (pin "1") (pinfunction "1_1") (pintype "passive"))
      (node (ref "U10") (pin "P$22") (pinfunction "~{CHG}_P$22") (pintype "output"))
    )
    (net (code "123") (name "Net-(U10-~{DOK})") (class "Default")
      (node (ref "R115") (pin "1") (pinfunction "1_1") (pintype "passive"))
      (node (ref "U10") (pin "P$26") (pinfunction "~{DOK}_P$26") (pintype "output"))
    )
    (net (code "124") (name "Net-(U10-~{DONE})") (class "Default")
      (node (ref "R111") (pin "1") (pinfunction "1_1") (pintype "passive"))
      (node (ref "U10") (pin "P$1") (pinfunction "~{DONE}_P$1") (pintype "output"))
    )
    (net (code "125") (name "Net-(U10-~{FLT})") (class "Default")
      (node (ref "R113") (pin "1") (pinfunction "1_1") (pintype "passive"))
      (node (ref "U10") (pin "P$28") (pinfunction "~{FLT}_P$28") (pintype "output"))
    )
    (net (code "126") (name "Net-(U10-~{OT})") (class "Default")
      (node (ref "R112") (pin "1") (pinfunction "1_1") (pintype "passive"))
      (node (ref "U10") (pin "P$25") (pinfunction "~{OT}_P$25") (pintype "output"))
    )
    (net (code "127") (name "Net-(U10-~{UOK})") (class "Default")
      (node (ref "R114") (pin "1") (pinfunction "1_1") (pintype "passive"))
      (node (ref "U10") (pin "P$27") (pinfunction "~{UOK}_P$27") (pintype "output"))
    )
    (net (code "128") (name "Net-(U11-BYPASS)") (class "Default")
      (node (ref "C40") (pin "1") (pinfunction "1_1") (pintype "passive"))
      (node (ref "U11") (pin "1") (pinfunction "BYPASS_1") (pintype "passive"))
    )
    (net (code "129") (name "Net-(U11-~{ERR})") (class "Default")
      (node (ref "R116") (pin "2") (pinfunction "2_2") (pintype "passive"))
      (node (ref "U11") (pin "7") (pinfunction "~{ERR}_7") (pintype "output"))
    )
    (net (code "130") (name "Net-(U12-BYPASS)") (class "Default")
      (node (ref "C39") (pin "1") (pinfunction "1_1") (pintype "passive"))
      (node (ref "U12") (pin "1") (pinfunction "BYPASS_1") (pintype "passive"))
    )
    (net (code "131") (name "Net-(U12-~{ERR})") (class "Default")
      (node (ref "R117") (pin "2") (pinfunction "2_2") (pintype "passive"))
      (node (ref "U12") (pin "7") (pinfunction "~{ERR}_7") (pintype "output"))
    )
    (net (code "132") (name "unconnected-(U$1-CARD_DETECT1-PadCD2)") (class "Default")
      (node (ref "U$1") (pin "CD2") (pinfunction "CARD_DETECT1_CD2") (pintype "passive"))
    )
    (net (code "133") (name "unconnected-(U$1-DAT1-Pad8)") (class "Default")
      (node (ref "U$1") (pin "8") (pinfunction "DAT1_8") (pintype "bidirectional"))
    )
    (net (code "134") (name "unconnected-(U$1-DAT2-Pad1)") (class "Default")
      (node (ref "U$1") (pin "1") (pinfunction "DAT2_1") (pintype "bidirectional"))
    )
    (net (code "135") (name "unconnected-(U1-P$3-Pad3)") (class "Default")
      (node (ref "U1") (pin "3") (pinfunction "P$3_3") (pintype "bidirectional"))
    )
    (net (code "136") (name "unconnected-(U1-P$33-Pad33)") (class "Default")
      (node (ref "U1") (pin "33") (pinfunction "P$33_33") (pintype "bidirectional"))
    )
    (net (code "137") (name "unconnected-(U1-P$34-Pad34)") (class "Default")
      (node (ref "U1") (pin "34") (pinfunction "P$34_34") (pintype "bidirectional"))
    )
    (net (code "138") (name "unconnected-(U1-P$35-Pad35)") (class "Default")
      (node (ref "U1") (pin "35") (pinfunction "P$35_35") (pintype "bidirectional"))
    )
    (net (code "139") (name "unconnected-(U1-P$36-Pad36)") (class "Default")
      (node (ref "U1") (pin "36") (pinfunction "P$36_36") (pintype "bidirectional"))
    )
    (net (code "140") (name "unconnected-(U1-P$37-Pad37)") (class "Default")
      (node (ref "U1") (pin "37") (pinfunction "P$37_37") (pintype "bidirectional"))
    )
    (net (code "141") (name "unconnected-(U1-P$38-Pad38)") (class "Default")
      (node (ref "U1") (pin "38") (pinfunction "P$38_38") (pintype "bidirectional"))
    )
    (net (code "142") (name "unconnected-(U1-P$40-Pad40)") (class "Default")
      (node (ref "U1") (pin "40") (pinfunction "P$40_40") (pintype "bidirectional"))
    )
    (net (code "143") (name "unconnected-(U2-AIO0-Pad30)") (class "Default")
      (node (ref "U2") (pin "30") (pinfunction "AIO0_30") (pintype "bidirectional"))
    )
    (net (code "144") (name "unconnected-(U2-AIO1-Pad35)") (class "Default")
      (node (ref "U2") (pin "35") (pinfunction "AIO1_35") (pintype "bidirectional"))
    )
    (net (code "145") (name "unconnected-(U2-PCMCLK-Pad7)") (class "Default")
      (node (ref "U2") (pin "7") (pinfunction "PCMCLK_7") (pintype "bidirectional"))
    )
    (net (code "146") (name "unconnected-(U2-PCMIN-Pad9)") (class "Default")
      (node (ref "U2") (pin "9") (pinfunction "PCMIN_9") (pintype "bidirectional"))
    )
    (net (code "147") (name "unconnected-(U2-PCMOUT-Pad10)") (class "Default")
      (node (ref "U2") (pin "10") (pinfunction "PCMOUT_10") (pintype "bidirectional"))
    )
    (net (code "148") (name "unconnected-(U2-PCMSYNC-Pad8)") (class "Default")
      (node (ref "U2") (pin "8") (pinfunction "PCMSYNC_8") (pintype "bidirectional"))
    )
    (net (code "149") (name "unconnected-(U2-PIO4-Pad22)") (class "Default")
      (node (ref "U2") (pin "22") (pinfunction "PIO4_22") (pintype "bidirectional"))
    )
    (net (code "150") (name "unconnected-(U2-PIO9-Pad32)") (class "Default")
      (node (ref "U2") (pin "32") (pinfunction "PIO9_32") (pintype "bidirectional"))
    )
    (net (code "151") (name "unconnected-(U2-PIO10-Pad33)") (class "Default")
      (node (ref "U2") (pin "33") (pinfunction "PIO10_33") (pintype "bidirectional"))
    )
    (net (code "152") (name "unconnected-(U2-PIO11-Pad34)") (class "Default")
      (node (ref "U2") (pin "34") (pinfunction "PIO11_34") (pintype "bidirectional"))
    )
    (net (code "153") (name "unconnected-(U2-SPICLK-Pad6)") (class "Default")
      (node (ref "U2") (pin "6") (pinfunction "SPICLK_6") (pintype "bidirectional"))
    )
    (net (code "154") (name "unconnected-(U2-SPICSB-Pad23)") (class "Default")
      (node (ref "U2") (pin "23") (pinfunction "SPICSB_23") (pintype "bidirectional"))
    )
    (net (code "155") (name "unconnected-(U2-SPIMISO-Pad24)") (class "Default")
      (node (ref "U2") (pin "24") (pinfunction "SPIMISO_24") (pintype "bidirectional"))
    )
    (net (code "156") (name "unconnected-(U2-SPIMOSI-Pad2)") (class "Default")
      (node (ref "U2") (pin "2") (pinfunction "SPIMOSI_2") (pintype "bidirectional"))
    )
    (net (code "157") (name "unconnected-(U2-UARTCTS-Pad16)") (class "Default")
      (node (ref "U2") (pin "16") (pinfunction "UARTCTS_16") (pintype "bidirectional"))
    )
    (net (code "158") (name "unconnected-(U2-UARTRTS-Pad15)") (class "Default")
      (node (ref "U2") (pin "15") (pinfunction "UARTRTS_15") (pintype "bidirectional"))
    )
    (net (code "159") (name "unconnected-(U2-USBD+-Pad17)") (class "Default")
      (node (ref "U2") (pin "17") (pinfunction "USBD+_17") (pintype "bidirectional"))
    )
    (net (code "160") (name "unconnected-(U2-USBD--Pad18)") (class "Default")
      (node (ref "U2") (pin "18") (pinfunction "USBD-_18") (pintype "bidirectional"))
    )
    (net (code "161") (name "unconnected-(U4-AIN4-Pad10)") (class "Default")
      (node (ref "U4") (pin "10") (pinfunction "AIN4_10") (pintype "input"))
    )
    (net (code "162") (name "unconnected-(U4-AIN5-Pad11)") (class "Default")
      (node (ref "U4") (pin "11") (pinfunction "AIN5_11") (pintype "input"))
    )
    (net (code "163") (name "unconnected-(U4-AIN6-Pad12)") (class "Default")
      (node (ref "U4") (pin "12") (pinfunction "AIN6_12") (pintype "input"))
    )
    (net (code "164") (name "unconnected-(U4-AIN7-Pad13)") (class "Default")
      (node (ref "U4") (pin "13") (pinfunction "AIN7_13") (pintype "input"))
    )
    (net (code "165") (name "unconnected-(U4-D0{slash}CLKOUT-Pad25)") (class "Default")
      (node (ref "U4") (pin "25") (pinfunction "D0/CLKOUT_25") (pintype "bidirectional"))
    )
    (net (code "166") (name "unconnected-(U4-D1-Pad26)") (class "Default")
      (node (ref "U4") (pin "26") (pinfunction "D1_26") (pintype "bidirectional"))
    )
    (net (code "167") (name "unconnected-(U4-D2-Pad27)") (class "Default")
      (node (ref "U4") (pin "27") (pinfunction "D2_27") (pintype "bidirectional"))
    )
    (net (code "168") (name "unconnected-(U4-D3-Pad28)") (class "Default")
      (node (ref "U4") (pin "28") (pinfunction "D3_28") (pintype "bidirectional"))
    )
    (net (code "169") (name "unconnected-(U5-NC3-Pad3)") (class "Default")
      (node (ref "U5") (pin "3") (pinfunction "NC3_3") (pintype "no_connect"))
    )
    (net (code "170") (name "unconnected-(U5-NC4-Pad4)") (class "Default")
      (node (ref "U5") (pin "4") (pinfunction "NC4_4") (pintype "no_connect"))
    )
    (net (code "171") (name "unconnected-(U11-NC-Pad2)") (class "Default")
      (node (ref "U11") (pin "2") (pinfunction "NC_2") (pintype "bidirectional"))
    )
    (net (code "172") (name "unconnected-(U12-NC-Pad2)") (class "Default")
      (node (ref "U12") (pin "2") (pinfunction "NC_2") (pintype "bidirectional"))
    )
  )
)
